# 4-DDR3_MEMORY.net
KiCad netlist of a schematic drawn in Altium Designer
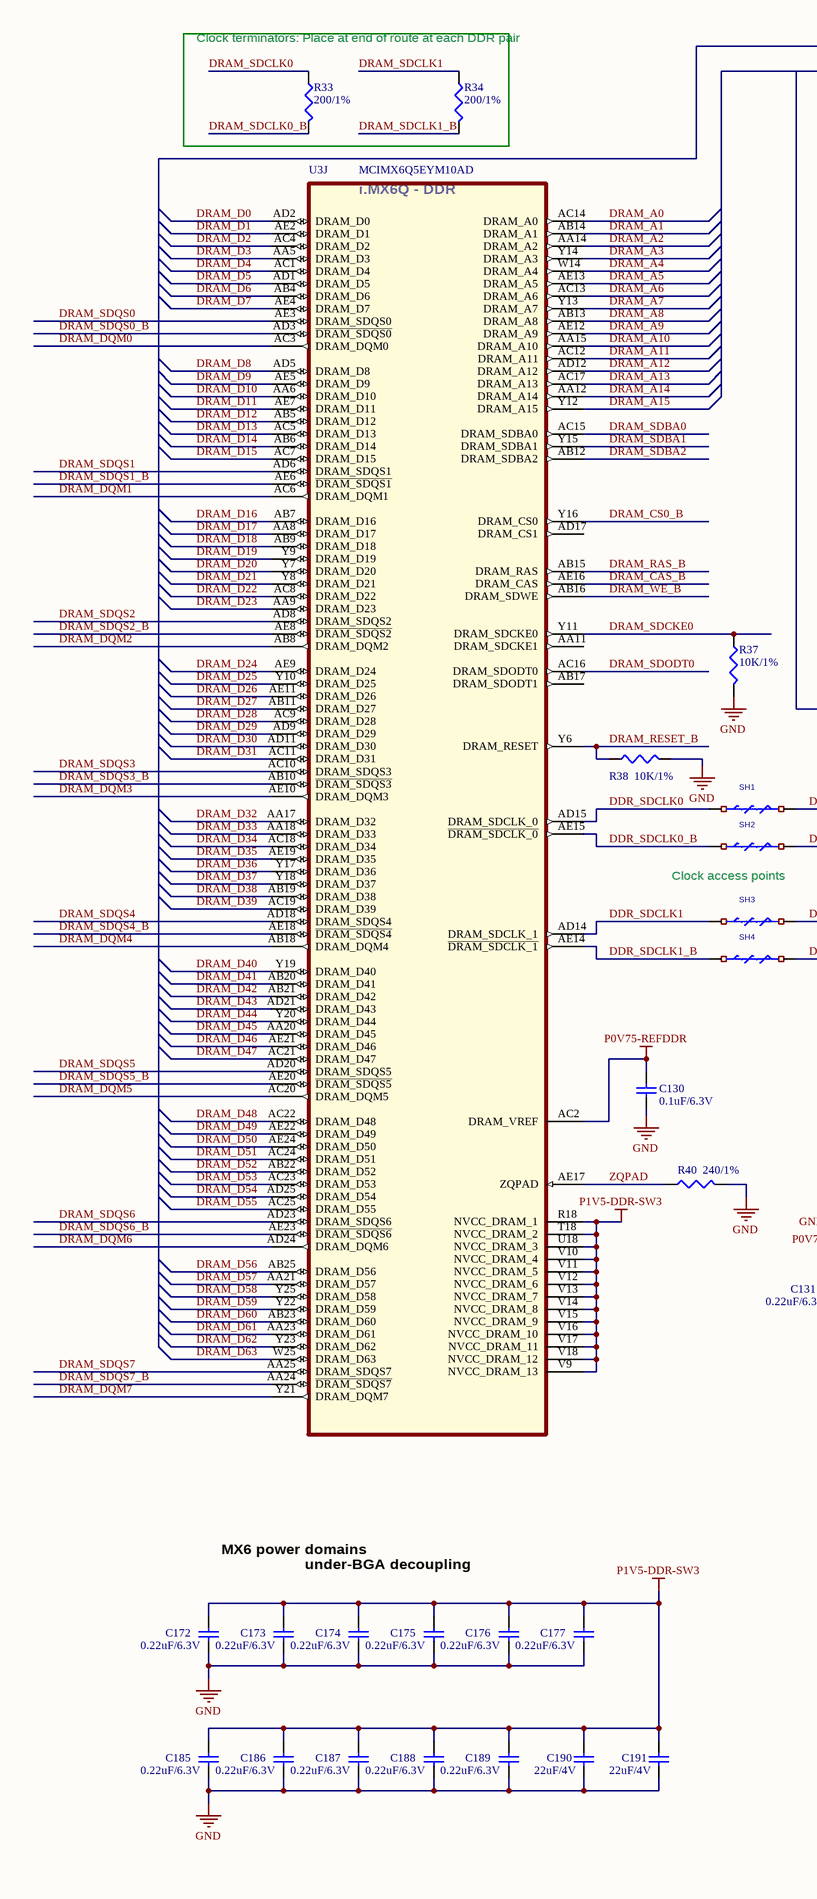
[diagram p0: 4-DDR3_MEMORY.SchDoc, left]
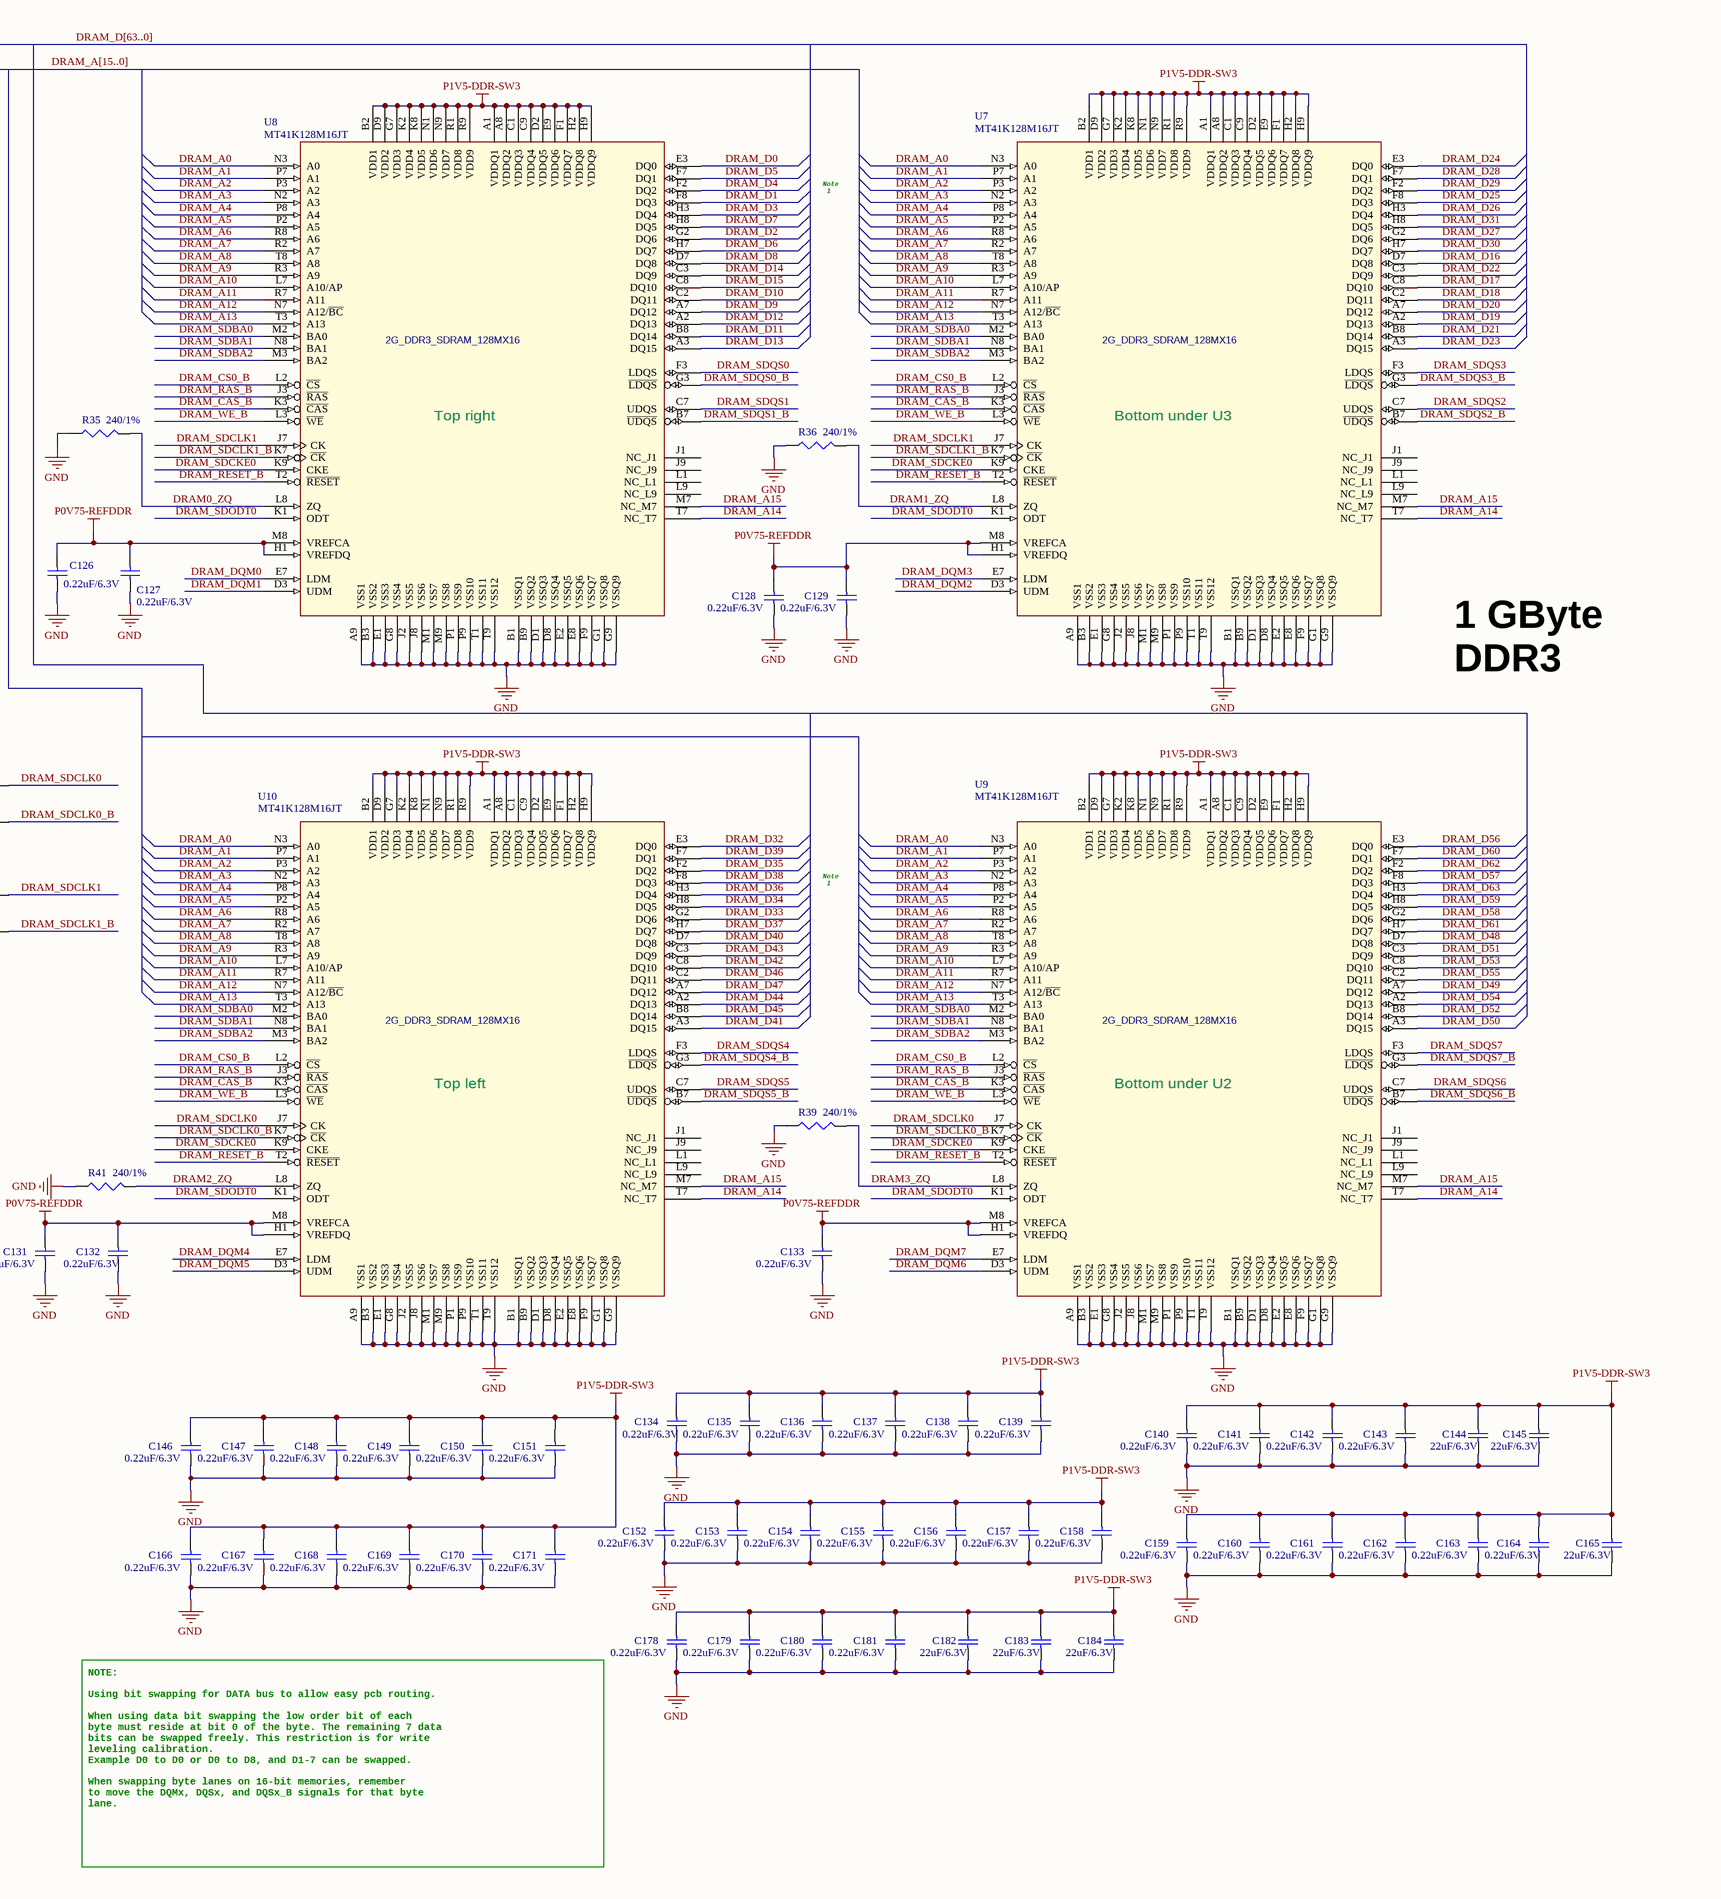
[diagram p1: 4-DDR3_MEMORY.SchDoc, right]

(export (version "E")
  (design (tool "Eeschema 10.0.6"))
  (components
    (comp (ref "C126")
      (value "0.22uF/6.3V")
      (footprint "0402_CC")
      (description "Capacitor")
      (fields (field (name "PUBLISHER") "Altium Limited"))
      (libsource (lib "Miscellaneous Devices") (part "Cap"))
    )
    (comp (ref "C127")
      (value "0.22uF/6.3V")
      (footprint "0402_CC")
      (description "Capacitor")
      (fields (field (name "PUBLISHER") "Altium Limited"))
      (libsource (lib "Miscellaneous Devices") (part "Cap"))
    )
    (comp (ref "C128")
      (value "0.22uF/6.3V")
      (footprint "0402_CC")
      (description "Capacitor")
      (fields (field (name "PUBLISHER") "Altium Limited"))
      (libsource (lib "Miscellaneous Devices") (part "Cap"))
    )
    (comp (ref "C129")
      (value "0.22uF/6.3V")
      (footprint "0402_CC")
      (description "Capacitor")
      (fields (field (name "PUBLISHER") "Altium Limited"))
      (libsource (lib "Miscellaneous Devices") (part "Cap"))
    )
    (comp (ref "C130")
      (value "0.1uF/6.3V")
      (footprint "0402_CC")
      (description "Capacitor")
      (fields (field (name "PUBLISHER") "Altium Limited"))
      (libsource (lib "Miscellaneous Devices") (part "Cap"))
    )
    (comp (ref "C131")
      (value "0.22uF/6.3V")
      (footprint "0402_CC")
      (description "Capacitor")
      (fields (field (name "PUBLISHER") "Altium Limited"))
      (libsource (lib "Miscellaneous Devices") (part "Cap"))
    )
    (comp (ref "C132")
      (value "0.22uF/6.3V")
      (footprint "0402_CC")
      (description "Capacitor")
      (fields (field (name "PUBLISHER") "Altium Limited"))
      (libsource (lib "Miscellaneous Devices") (part "Cap"))
    )
    (comp (ref "C133")
      (value "0.22uF/6.3V")
      (footprint "0402_CC")
      (description "Capacitor")
      (fields (field (name "PUBLISHER") "Altium Limited"))
      (libsource (lib "Miscellaneous Devices") (part "Cap"))
    )
    (comp (ref "C134")
      (value "0.22uF/6.3V")
      (footprint "0402_CC")
      (description "Capacitor")
      (fields (field (name "PUBLISHER") "Altium Limited"))
      (libsource (lib "Miscellaneous Devices") (part "Cap"))
    )
    (comp (ref "C135")
      (value "0.22uF/6.3V")
      (footprint "0402_CC")
      (description "Capacitor")
      (fields (field (name "PUBLISHER") "Altium Limited"))
      (libsource (lib "Miscellaneous Devices") (part "Cap"))
    )
    (comp (ref "C136")
      (value "0.22uF/6.3V")
      (footprint "0402_CC")
      (description "Capacitor")
      (fields (field (name "PUBLISHER") "Altium Limited"))
      (libsource (lib "Miscellaneous Devices") (part "Cap"))
    )
    (comp (ref "C137")
      (value "0.22uF/6.3V")
      (footprint "0402_CC")
      (description "Capacitor")
      (fields (field (name "PUBLISHER") "Altium Limited"))
      (libsource (lib "Miscellaneous Devices") (part "Cap"))
    )
    (comp (ref "C138")
      (value "0.22uF/6.3V")
      (footprint "0402_CC")
      (description "Capacitor")
      (fields (field (name "PUBLISHER") "Altium Limited"))
      (libsource (lib "Miscellaneous Devices") (part "Cap"))
    )
    (comp (ref "C139")
      (value "0.22uF/6.3V")
      (footprint "0402_CC")
      (description "Capacitor")
      (fields (field (name "PUBLISHER") "Altium Limited"))
      (libsource (lib "Miscellaneous Devices") (part "Cap"))
    )
    (comp (ref "C140")
      (value "0.22uF/6.3V")
      (footprint "0402_CC")
      (description "Capacitor")
      (fields (field (name "PUBLISHER") "Altium Limited"))
      (libsource (lib "Miscellaneous Devices") (part "Cap"))
    )
    (comp (ref "C141")
      (value "0.22uF/6.3V")
      (footprint "0402_CC")
      (description "Capacitor")
      (fields (field (name "PUBLISHER") "Altium Limited"))
      (libsource (lib "Miscellaneous Devices") (part "Cap"))
    )
    (comp (ref "C142")
      (value "0.22uF/6.3V")
      (footprint "0402_CC")
      (description "Capacitor")
      (fields (field (name "PUBLISHER") "Altium Limited"))
      (libsource (lib "Miscellaneous Devices") (part "Cap"))
    )
    (comp (ref "C143")
      (value "0.22uF/6.3V")
      (footprint "0402_CC")
      (description "Capacitor")
      (fields (field (name "PUBLISHER") "Altium Limited"))
      (libsource (lib "Miscellaneous Devices") (part "Cap"))
    )
    (comp (ref "C144")
      (value "22uF/6.3V")
      (footprint "0805_CC")
      (description "Capacitor")
      (fields (field (name "PUBLISHER") "Altium Limited"))
      (libsource (lib "Miscellaneous Devices") (part "Cap"))
    )
    (comp (ref "C145")
      (value "22uF/6.3V")
      (footprint "0805_CC")
      (description "Capacitor")
      (fields (field (name "PUBLISHER") "Altium Limited"))
      (libsource (lib "Miscellaneous Devices") (part "Cap"))
    )
    (comp (ref "C146")
      (value "0.22uF/6.3V")
      (footprint "0402_CC")
      (description "Capacitor")
      (fields (field (name "PUBLISHER") "Altium Limited"))
      (libsource (lib "Miscellaneous Devices") (part "Cap"))
    )
    (comp (ref "C147")
      (value "0.22uF/6.3V")
      (footprint "0402_CC")
      (description "Capacitor")
      (fields (field (name "PUBLISHER") "Altium Limited"))
      (libsource (lib "Miscellaneous Devices") (part "Cap"))
    )
    (comp (ref "C148")
      (value "0.22uF/6.3V")
      (footprint "0402_CC")
      (description "Capacitor")
      (fields (field (name "PUBLISHER") "Altium Limited"))
      (libsource (lib "Miscellaneous Devices") (part "Cap"))
    )
    (comp (ref "C149")
      (value "0.22uF/6.3V")
      (footprint "0402_CC")
      (description "Capacitor")
      (fields (field (name "PUBLISHER") "Altium Limited"))
      (libsource (lib "Miscellaneous Devices") (part "Cap"))
    )
    (comp (ref "C150")
      (value "0.22uF/6.3V")
      (footprint "0402_CC")
      (description "Capacitor")
      (fields (field (name "PUBLISHER") "Altium Limited"))
      (libsource (lib "Miscellaneous Devices") (part "Cap"))
    )
    (comp (ref "C151")
      (value "0.22uF/6.3V")
      (footprint "0402_CC")
      (description "Capacitor")
      (fields (field (name "PUBLISHER") "Altium Limited"))
      (libsource (lib "Miscellaneous Devices") (part "Cap"))
    )
    (comp (ref "C152")
      (value "0.22uF/6.3V")
      (footprint "0402_CC")
      (description "Capacitor")
      (fields (field (name "PUBLISHER") "Altium Limited"))
      (libsource (lib "Miscellaneous Devices") (part "Cap"))
    )
    (comp (ref "C153")
      (value "0.22uF/6.3V")
      (footprint "0402_CC")
      (description "Capacitor")
      (fields (field (name "PUBLISHER") "Altium Limited"))
      (libsource (lib "Miscellaneous Devices") (part "Cap"))
    )
    (comp (ref "C154")
      (value "0.22uF/6.3V")
      (footprint "0402_CC")
      (description "Capacitor")
      (fields (field (name "PUBLISHER") "Altium Limited"))
      (libsource (lib "Miscellaneous Devices") (part "Cap"))
    )
    (comp (ref "C155")
      (value "0.22uF/6.3V")
      (footprint "0402_CC")
      (description "Capacitor")
      (fields (field (name "PUBLISHER") "Altium Limited"))
      (libsource (lib "Miscellaneous Devices") (part "Cap"))
    )
    (comp (ref "C156")
      (value "0.22uF/6.3V")
      (footprint "0402_CC")
      (description "Capacitor")
      (fields (field (name "PUBLISHER") "Altium Limited"))
      (libsource (lib "Miscellaneous Devices") (part "Cap"))
    )
    (comp (ref "C157")
      (value "0.22uF/6.3V")
      (footprint "0402_CC")
      (description "Capacitor")
      (fields (field (name "PUBLISHER") "Altium Limited"))
      (libsource (lib "Miscellaneous Devices") (part "Cap"))
    )
    (comp (ref "C158")
      (value "0.22uF/6.3V")
      (footprint "0402_CC")
      (description "Capacitor")
      (fields (field (name "PUBLISHER") "Altium Limited"))
      (libsource (lib "Miscellaneous Devices") (part "Cap"))
    )
    (comp (ref "C159")
      (value "0.22uF/6.3V")
      (footprint "0402_CC")
      (description "Capacitor")
      (fields (field (name "PUBLISHER") "Altium Limited"))
      (libsource (lib "Miscellaneous Devices") (part "Cap"))
    )
    (comp (ref "C160")
      (value "0.22uF/6.3V")
      (footprint "0402_CC")
      (description "Capacitor")
      (fields (field (name "PUBLISHER") "Altium Limited"))
      (libsource (lib "Miscellaneous Devices") (part "Cap"))
    )
    (comp (ref "C161")
      (value "0.22uF/6.3V")
      (footprint "0402_CC")
      (description "Capacitor")
      (fields (field (name "PUBLISHER") "Altium Limited"))
      (libsource (lib "Miscellaneous Devices") (part "Cap"))
    )
    (comp (ref "C162")
      (value "0.22uF/6.3V")
      (footprint "0402_CC")
      (description "Capacitor")
      (fields (field (name "PUBLISHER") "Altium Limited"))
      (libsource (lib "Miscellaneous Devices") (part "Cap"))
    )
    (comp (ref "C163")
      (value "0.22uF/6.3V")
      (footprint "0402_CC")
      (description "Capacitor")
      (fields (field (name "PUBLISHER") "Altium Limited"))
      (libsource (lib "Miscellaneous Devices") (part "Cap"))
    )
    (comp (ref "C164")
      (value "0.22uF/6.3V")
      (footprint "0402_CC")
      (description "Capacitor")
      (fields (field (name "PUBLISHER") "Altium Limited"))
      (libsource (lib "Miscellaneous Devices") (part "Cap"))
    )
    (comp (ref "C165")
      (value "22uF/6.3V")
      (footprint "0805_CC")
      (description "Capacitor")
      (fields (field (name "PUBLISHER") "Altium Limited"))
      (libsource (lib "Miscellaneous Devices") (part "Cap"))
    )
    (comp (ref "C166")
      (value "0.22uF/6.3V")
      (footprint "0402_CC")
      (description "Capacitor")
      (fields (field (name "PUBLISHER") "Altium Limited"))
      (libsource (lib "Miscellaneous Devices") (part "Cap"))
    )
    (comp (ref "C167")
      (value "0.22uF/6.3V")
      (footprint "0402_CC")
      (description "Capacitor")
      (fields (field (name "PUBLISHER") "Altium Limited"))
      (libsource (lib "Miscellaneous Devices") (part "Cap"))
    )
    (comp (ref "C168")
      (value "0.22uF/6.3V")
      (footprint "0402_CC")
      (description "Capacitor")
      (fields (field (name "PUBLISHER") "Altium Limited"))
      (libsource (lib "Miscellaneous Devices") (part "Cap"))
    )
    (comp (ref "C169")
      (value "0.22uF/6.3V")
      (footprint "0402_CC")
      (description "Capacitor")
      (fields (field (name "PUBLISHER") "Altium Limited"))
      (libsource (lib "Miscellaneous Devices") (part "Cap"))
    )
    (comp (ref "C170")
      (value "0.22uF/6.3V")
      (footprint "0402_CC")
      (description "Capacitor")
      (fields (field (name "PUBLISHER") "Altium Limited"))
      (libsource (lib "Miscellaneous Devices") (part "Cap"))
    )
    (comp (ref "C171")
      (value "0.22uF/6.3V")
      (footprint "0402_CC")
      (description "Capacitor")
      (fields (field (name "PUBLISHER") "Altium Limited"))
      (libsource (lib "Miscellaneous Devices") (part "Cap"))
    )
    (comp (ref "C172")
      (value "0.22uF/6.3V")
      (footprint "0201_CC")
      (description "Capacitor")
      (fields (field (name "PUBLISHER") "Altium Limited"))
      (libsource (lib "Miscellaneous Devices") (part "Cap"))
    )
    (comp (ref "C173")
      (value "0.22uF/6.3V")
      (footprint "0201_CC")
      (description "Capacitor")
      (fields (field (name "PUBLISHER") "Altium Limited"))
      (libsource (lib "Miscellaneous Devices") (part "Cap"))
    )
    (comp (ref "C174")
      (value "0.22uF/6.3V")
      (footprint "0201_CC")
      (description "Capacitor")
      (fields (field (name "PUBLISHER") "Altium Limited"))
      (libsource (lib "Miscellaneous Devices") (part "Cap"))
    )
    (comp (ref "C175")
      (value "0.22uF/6.3V")
      (footprint "0201_CC")
      (description "Capacitor")
      (fields (field (name "PUBLISHER") "Altium Limited"))
      (libsource (lib "Miscellaneous Devices") (part "Cap"))
    )
    (comp (ref "C176")
      (value "0.22uF/6.3V")
      (footprint "0201_CC")
      (description "Capacitor")
      (fields (field (name "PUBLISHER") "Altium Limited"))
      (libsource (lib "Miscellaneous Devices") (part "Cap"))
    )
    (comp (ref "C177")
      (value "0.22uF/6.3V")
      (footprint "0201_CC")
      (description "Capacitor")
      (fields (field (name "PUBLISHER") "Altium Limited"))
      (libsource (lib "Miscellaneous Devices") (part "Cap"))
    )
    (comp (ref "C178")
      (value "0.22uF/6.3V")
      (footprint "0402_CC")
      (description "Capacitor")
      (fields (field (name "PUBLISHER") "Altium Limited"))
      (libsource (lib "Miscellaneous Devices") (part "Cap"))
    )
    (comp (ref "C179")
      (value "0.22uF/6.3V")
      (footprint "0402_CC")
      (description "Capacitor")
      (fields (field (name "PUBLISHER") "Altium Limited"))
      (libsource (lib "Miscellaneous Devices") (part "Cap"))
    )
    (comp (ref "C180")
      (value "0.22uF/6.3V")
      (footprint "0402_CC")
      (description "Capacitor")
      (fields (field (name "PUBLISHER") "Altium Limited"))
      (libsource (lib "Miscellaneous Devices") (part "Cap"))
    )
    (comp (ref "C181")
      (value "0.22uF/6.3V")
      (footprint "0402_CC")
      (description "Capacitor")
      (fields (field (name "PUBLISHER") "Altium Limited"))
      (libsource (lib "Miscellaneous Devices") (part "Cap"))
    )
    (comp (ref "C182")
      (value "22uF/6.3V")
      (footprint "0805_CC")
      (description "Capacitor")
      (fields (field (name "PUBLISHER") "Altium Limited"))
      (libsource (lib "Miscellaneous Devices") (part "Cap"))
    )
    (comp (ref "C183")
      (value "22uF/6.3V")
      (footprint "0805_CC")
      (description "Capacitor")
      (fields (field (name "PUBLISHER") "Altium Limited"))
      (libsource (lib "Miscellaneous Devices") (part "Cap"))
    )
    (comp (ref "C184")
      (value "22uF/6.3V")
      (footprint "0805_CC")
      (description "Capacitor")
      (fields (field (name "PUBLISHER") "Altium Limited"))
      (libsource (lib "Miscellaneous Devices") (part "Cap"))
    )
    (comp (ref "C185")
      (value "0.22uF/6.3V")
      (footprint "0201_CC")
      (description "Capacitor")
      (fields (field (name "PUBLISHER") "Altium Limited"))
      (libsource (lib "Miscellaneous Devices") (part "Cap"))
    )
    (comp (ref "C186")
      (value "0.22uF/6.3V")
      (footprint "0201_CC")
      (description "Capacitor")
      (fields (field (name "PUBLISHER") "Altium Limited"))
      (libsource (lib "Miscellaneous Devices") (part "Cap"))
    )
    (comp (ref "C187")
      (value "0.22uF/6.3V")
      (footprint "0201_CC")
      (description "Capacitor")
      (fields (field (name "PUBLISHER") "Altium Limited"))
      (libsource (lib "Miscellaneous Devices") (part "Cap"))
    )
    (comp (ref "C188")
      (value "0.22uF/6.3V")
      (footprint "0201_CC")
      (description "Capacitor")
      (fields (field (name "PUBLISHER") "Altium Limited"))
      (libsource (lib "Miscellaneous Devices") (part "Cap"))
    )
    (comp (ref "C189")
      (value "0.22uF/6.3V")
      (footprint "0201_CC")
      (description "Capacitor")
      (fields (field (name "PUBLISHER") "Altium Limited"))
      (libsource (lib "Miscellaneous Devices") (part "Cap"))
    )
    (comp (ref "C190")
      (value "22uF/4V")
      (footprint "0603_CC")
      (description "Capacitor")
      (fields (field (name "PUBLISHER") "Altium Limited"))
      (libsource (lib "Miscellaneous Devices") (part "Cap"))
    )
    (comp (ref "C191")
      (value "22uF/4V")
      (footprint "0603_CC")
      (description "Capacitor")
      (fields (field (name "PUBLISHER") "Altium Limited"))
      (libsource (lib "Miscellaneous Devices") (part "Cap"))
    )
    (comp (ref "R33")
      (value "200/1%")
      (footprint "0402_CC")
      (description "Resistor")
      (fields (field (name "PUBLISHER") "Altium Limited"))
      (libsource (lib "Miscellaneous Devices") (part "Res3"))
    )
    (comp (ref "R34")
      (value "200/1%")
      (footprint "0402_CC")
      (description "Resistor")
      (fields (field (name "PUBLISHER") "Altium Limited"))
      (libsource (lib "Miscellaneous Devices") (part "Res3"))
    )
    (comp (ref "R35")
      (value "240/1%")
      (footprint "0402_CC")
      (description "Resistor")
      (fields (field (name "PUBLISHER") "Altium Limited"))
      (libsource (lib "Miscellaneous Devices") (part "Res3"))
    )
    (comp (ref "R36")
      (value "240/1%")
      (footprint "0402_CC")
      (description "Resistor")
      (fields (field (name "PUBLISHER") "Altium Limited"))
      (libsource (lib "Miscellaneous Devices") (part "Res3"))
    )
    (comp (ref "R37")
      (value "10K/1%")
      (footprint "0402_CC")
      (description "Resistor")
      (fields (field (name "PUBLISHER") "Altium Limited"))
      (libsource (lib "Miscellaneous Devices") (part "Res3"))
    )
    (comp (ref "R38")
      (value "10K/1%")
      (footprint "0402_CC")
      (description "Resistor")
      (fields (field (name "PUBLISHER") "Altium Limited"))
      (libsource (lib "Miscellaneous Devices") (part "Res3"))
    )
    (comp (ref "R39")
      (value "240/1%")
      (footprint "0402_CC")
      (description "Resistor")
      (fields (field (name "PUBLISHER") "Altium Limited"))
      (libsource (lib "Miscellaneous Devices") (part "Res3"))
    )
    (comp (ref "R40")
      (value "240/1%")
      (footprint "0402_CC")
      (description "Resistor")
      (fields (field (name "PUBLISHER") "Altium Limited"))
      (libsource (lib "Miscellaneous Devices") (part "Res3"))
    )
    (comp (ref "R41")
      (value "240/1%")
      (footprint "0402_CC")
      (description "Resistor")
      (fields (field (name "PUBLISHER") "Altium Limited"))
      (libsource (lib "Miscellaneous Devices") (part "Res3"))
    )
    (comp (ref "SH1")
      (value "0")
      (footprint "0201_CC")
      (description "ZERO OHM CUT TRACE 0201 PADS; NO PART TO ORDER")
      (libsource (lib "*") (part "RES_SHORT-2"))
    )
    (comp (ref "SH2")
      (value "0")
      (footprint "0201_CC")
      (description "ZERO OHM CUT TRACE 0201 PADS; NO PART TO ORDER")
      (libsource (lib "*") (part "RES_SHORT-2"))
    )
    (comp (ref "SH3")
      (value "0")
      (footprint "0201_CC")
      (description "ZERO OHM CUT TRACE 0201 PADS; NO PART TO ORDER")
      (libsource (lib "*") (part "RES_SHORT-2"))
    )
    (comp (ref "SH4")
      (value "0")
      (footprint "0201_CC")
      (description "ZERO OHM CUT TRACE 0201 PADS; NO PART TO ORDER")
      (libsource (lib "*") (part "RES_SHORT-2"))
    )
    (comp (ref "U3")
      (value "MCIMX6Q5EYM10AD")
      (footprint "FCPBGA")
      (description "IC MCU MX6QUAD ARM CORTEX-A9 FCPBGA624")
      (libsource (lib "*") (part "PCIMX6Q6VV1A"))
    )
    (comp (ref "U7")
      (value "MT41K128M16JT")
      (footprint "BGA96")
      (description "IC MEM DDR3 SDRAM 2Gb 128MX16 1.35V FBGA96")
      (libsource (lib "*") (part "2G_DDR3_SDRAM_128MX16_96P"))
    )
    (comp (ref "U8")
      (value "MT41K128M16JT")
      (footprint "BGA96")
      (description "IC MEM DDR3 SDRAM 2Gb 128MX16 1.35V FBGA96")
      (libsource (lib "*") (part "2G_DDR3_SDRAM_128MX16_96P"))
    )
    (comp (ref "U9")
      (value "MT41K128M16JT")
      (footprint "BGA96")
      (description "IC MEM DDR3 SDRAM 2Gb 128MX16 1.35V FBGA96")
      (libsource (lib "*") (part "2G_DDR3_SDRAM_128MX16_96P"))
    )
    (comp (ref "U10")
      (value "MT41K128M16JT")
      (footprint "BGA96")
      (description "IC MEM DDR3 SDRAM 2Gb 128MX16 1.35V FBGA96")
      (libsource (lib "*") (part "2G_DDR3_SDRAM_128MX16_96P"))
    )
  )
  (nets
    (net (code "1") (name "/DDR_SDCLK0") (class "Default")
      (node (ref "SH1") (pin "1") (pinfunction "1_1") (pintype "passive"))
      (node (ref "U3") (pin "AD15") (pinfunction "DRAM_SDCLK_0_AD15") (pintype "output"))
    )
    (net (code "2") (name "/DDR_SDCLK0_B") (class "Default")
      (node (ref "SH2") (pin "1") (pinfunction "1_1") (pintype "passive"))
      (node (ref "U3") (pin "AE15") (pinfunction "~{DRAM_SDCLK_0}_AE15") (pintype "output"))
    )
    (net (code "3") (name "/DDR_SDCLK1") (class "Default")
      (node (ref "SH3") (pin "1") (pinfunction "1_1") (pintype "passive"))
      (node (ref "U3") (pin "AD14") (pinfunction "DRAM_SDCLK_1_AD14") (pintype "output"))
    )
    (net (code "4") (name "/DDR_SDCLK1_B") (class "Default")
      (node (ref "SH4") (pin "1") (pinfunction "1_1") (pintype "passive"))
      (node (ref "U3") (pin "AE14") (pinfunction "~{DRAM_SDCLK_1}_AE14") (pintype "output"))
    )
    (net (code "5") (name "/DRAM0_ZQ") (class "Default")
      (node (ref "R35") (pin "2") (pinfunction "2_2") (pintype "passive"))
      (node (ref "U8") (pin "L8") (pinfunction "ZQ_L8") (pintype "input"))
    )
    (net (code "6") (name "/DRAM1_ZQ") (class "Default")
      (node (ref "R36") (pin "2") (pinfunction "2_2") (pintype "passive"))
      (node (ref "U7") (pin "L8") (pinfunction "ZQ_L8") (pintype "input"))
    )
    (net (code "7") (name "/DRAM2_ZQ") (class "Default")
      (node (ref "R41") (pin "2") (pinfunction "2_2") (pintype "passive"))
      (node (ref "U10") (pin "L8") (pinfunction "ZQ_L8") (pintype "input"))
    )
    (net (code "8") (name "/DRAM3_ZQ") (class "Default")
      (node (ref "R39") (pin "2") (pinfunction "2_2") (pintype "passive"))
      (node (ref "U9") (pin "L8") (pinfunction "ZQ_L8") (pintype "input"))
    )
    (net (code "9") (name "/DRAM_A0") (class "Default")
      (node (ref "U10") (pin "N3") (pinfunction "A0_N3") (pintype "input"))
      (node (ref "U3") (pin "AC14") (pinfunction "DRAM_A0_AC14") (pintype "output"))
      (node (ref "U7") (pin "N3") (pinfunction "A0_N3") (pintype "input"))
      (node (ref "U8") (pin "N3") (pinfunction "A0_N3") (pintype "input"))
      (node (ref "U9") (pin "N3") (pinfunction "A0_N3") (pintype "input"))
    )
    (net (code "10") (name "/DRAM_A1") (class "Default")
      (node (ref "U10") (pin "P7") (pinfunction "A1_P7") (pintype "input"))
      (node (ref "U3") (pin "AB14") (pinfunction "DRAM_A1_AB14") (pintype "output"))
      (node (ref "U7") (pin "P7") (pinfunction "A1_P7") (pintype "input"))
      (node (ref "U8") (pin "P7") (pinfunction "A1_P7") (pintype "input"))
      (node (ref "U9") (pin "P7") (pinfunction "A1_P7") (pintype "input"))
    )
    (net (code "11") (name "/DRAM_A2") (class "Default")
      (node (ref "U10") (pin "P3") (pinfunction "A2_P3") (pintype "input"))
      (node (ref "U3") (pin "AA14") (pinfunction "DRAM_A2_AA14") (pintype "output"))
      (node (ref "U7") (pin "P3") (pinfunction "A2_P3") (pintype "input"))
      (node (ref "U8") (pin "P3") (pinfunction "A2_P3") (pintype "input"))
      (node (ref "U9") (pin "P3") (pinfunction "A2_P3") (pintype "input"))
    )
    (net (code "12") (name "/DRAM_A3") (class "Default")
      (node (ref "U10") (pin "N2") (pinfunction "A3_N2") (pintype "input"))
      (node (ref "U3") (pin "Y14") (pinfunction "DRAM_A3_Y14") (pintype "output"))
      (node (ref "U7") (pin "N2") (pinfunction "A3_N2") (pintype "input"))
      (node (ref "U8") (pin "N2") (pinfunction "A3_N2") (pintype "input"))
      (node (ref "U9") (pin "N2") (pinfunction "A3_N2") (pintype "input"))
    )
    (net (code "13") (name "/DRAM_A4") (class "Default")
      (node (ref "U10") (pin "P8") (pinfunction "A4_P8") (pintype "input"))
      (node (ref "U3") (pin "W14") (pinfunction "DRAM_A4_W14") (pintype "output"))
      (node (ref "U7") (pin "P8") (pinfunction "A4_P8") (pintype "input"))
      (node (ref "U8") (pin "P8") (pinfunction "A4_P8") (pintype "input"))
      (node (ref "U9") (pin "P8") (pinfunction "A4_P8") (pintype "input"))
    )
    (net (code "14") (name "/DRAM_A5") (class "Default")
      (node (ref "U10") (pin "P2") (pinfunction "A5_P2") (pintype "input"))
      (node (ref "U3") (pin "AE13") (pinfunction "DRAM_A5_AE13") (pintype "output"))
      (node (ref "U7") (pin "P2") (pinfunction "A5_P2") (pintype "input"))
      (node (ref "U8") (pin "P2") (pinfunction "A5_P2") (pintype "input"))
      (node (ref "U9") (pin "P2") (pinfunction "A5_P2") (pintype "input"))
    )
    (net (code "15") (name "/DRAM_A6") (class "Default")
      (node (ref "U10") (pin "R8") (pinfunction "A6_R8") (pintype "input"))
      (node (ref "U3") (pin "AC13") (pinfunction "DRAM_A6_AC13") (pintype "output"))
      (node (ref "U7") (pin "R8") (pinfunction "A6_R8") (pintype "input"))
      (node (ref "U8") (pin "R8") (pinfunction "A6_R8") (pintype "input"))
      (node (ref "U9") (pin "R8") (pinfunction "A6_R8") (pintype "input"))
    )
    (net (code "16") (name "/DRAM_A7") (class "Default")
      (node (ref "U10") (pin "R2") (pinfunction "A7_R2") (pintype "input"))
      (node (ref "U3") (pin "Y13") (pinfunction "DRAM_A7_Y13") (pintype "output"))
      (node (ref "U7") (pin "R2") (pinfunction "A7_R2") (pintype "input"))
      (node (ref "U8") (pin "R2") (pinfunction "A7_R2") (pintype "input"))
      (node (ref "U9") (pin "R2") (pinfunction "A7_R2") (pintype "input"))
    )
    (net (code "17") (name "/DRAM_A8") (class "Default")
      (node (ref "U10") (pin "T8") (pinfunction "A8_T8") (pintype "input"))
      (node (ref "U3") (pin "AB13") (pinfunction "DRAM_A8_AB13") (pintype "output"))
      (node (ref "U7") (pin "T8") (pinfunction "A8_T8") (pintype "input"))
      (node (ref "U8") (pin "T8") (pinfunction "A8_T8") (pintype "input"))
      (node (ref "U9") (pin "T8") (pinfunction "A8_T8") (pintype "input"))
    )
    (net (code "18") (name "/DRAM_A9") (class "Default")
      (node (ref "U10") (pin "R3") (pinfunction "A9_R3") (pintype "input"))
      (node (ref "U3") (pin "AE12") (pinfunction "DRAM_A9_AE12") (pintype "output"))
      (node (ref "U7") (pin "R3") (pinfunction "A9_R3") (pintype "input"))
      (node (ref "U8") (pin "R3") (pinfunction "A9_R3") (pintype "input"))
      (node (ref "U9") (pin "R3") (pinfunction "A9_R3") (pintype "input"))
    )
    (net (code "19") (name "/DRAM_A10") (class "Default")
      (node (ref "U10") (pin "L7") (pinfunction "A10/AP_L7") (pintype "input"))
      (node (ref "U3") (pin "AA15") (pinfunction "DRAM_A10_AA15") (pintype "output"))
      (node (ref "U7") (pin "L7") (pinfunction "A10/AP_L7") (pintype "input"))
      (node (ref "U8") (pin "L7") (pinfunction "A10/AP_L7") (pintype "input"))
      (node (ref "U9") (pin "L7") (pinfunction "A10/AP_L7") (pintype "input"))
    )
    (net (code "20") (name "/DRAM_A11") (class "Default")
      (node (ref "U10") (pin "R7") (pinfunction "A11_R7") (pintype "input"))
      (node (ref "U3") (pin "AC12") (pinfunction "DRAM_A11_AC12") (pintype "output"))
      (node (ref "U7") (pin "R7") (pinfunction "A11_R7") (pintype "input"))
      (node (ref "U8") (pin "R7") (pinfunction "A11_R7") (pintype "input"))
      (node (ref "U9") (pin "R7") (pinfunction "A11_R7") (pintype "input"))
    )
    (net (code "21") (name "/DRAM_A12") (class "Default")
      (node (ref "U10") (pin "N7") (pinfunction "A12/~{BC}_N7") (pintype "input"))
      (node (ref "U3") (pin "AD12") (pinfunction "DRAM_A12_AD12") (pintype "output"))
      (node (ref "U7") (pin "N7") (pinfunction "A12/~{BC}_N7") (pintype "input"))
      (node (ref "U8") (pin "N7") (pinfunction "A12/~{BC}_N7") (pintype "input"))
      (node (ref "U9") (pin "N7") (pinfunction "A12/~{BC}_N7") (pintype "input"))
    )
    (net (code "22") (name "/DRAM_A13") (class "Default")
      (node (ref "U10") (pin "T3") (pinfunction "A13_T3") (pintype "input"))
      (node (ref "U3") (pin "AC17") (pinfunction "DRAM_A13_AC17") (pintype "output"))
      (node (ref "U7") (pin "T3") (pinfunction "A13_T3") (pintype "input"))
      (node (ref "U8") (pin "T3") (pinfunction "A13_T3") (pintype "input"))
      (node (ref "U9") (pin "T3") (pinfunction "A13_T3") (pintype "input"))
    )
    (net (code "23") (name "/DRAM_A14") (class "Default")
      (node (ref "U10") (pin "T7") (pinfunction "NC_T7_T7") (pintype "passive"))
      (node (ref "U3") (pin "AA12") (pinfunction "DRAM_A14_AA12") (pintype "output"))
      (node (ref "U7") (pin "T7") (pinfunction "NC_T7_T7") (pintype "passive"))
      (node (ref "U8") (pin "T7") (pinfunction "NC_T7_T7") (pintype "passive"))
      (node (ref "U9") (pin "T7") (pinfunction "NC_T7_T7") (pintype "passive"))
    )
    (net (code "24") (name "/DRAM_A15") (class "Default")
      (node (ref "U10") (pin "M7") (pinfunction "NC_M7_M7") (pintype "passive"))
      (node (ref "U3") (pin "Y12") (pinfunction "DRAM_A15_Y12") (pintype "output"))
      (node (ref "U7") (pin "M7") (pinfunction "NC_M7_M7") (pintype "passive"))
      (node (ref "U8") (pin "M7") (pinfunction "NC_M7_M7") (pintype "passive"))
      (node (ref "U9") (pin "M7") (pinfunction "NC_M7_M7") (pintype "passive"))
    )
    (net (code "26") (name "/DRAM_CAS_B") (class "Default")
      (node (ref "U10") (pin "K3") (pinfunction "~{CAS}_K3") (pintype "input"))
      (node (ref "U3") (pin "AE16") (pinfunction "DRAM_CAS_AE16") (pintype "output"))
      (node (ref "U7") (pin "K3") (pinfunction "~{CAS}_K3") (pintype "input"))
      (node (ref "U8") (pin "K3") (pinfunction "~{CAS}_K3") (pintype "input"))
      (node (ref "U9") (pin "K3") (pinfunction "~{CAS}_K3") (pintype "input"))
    )
    (net (code "27") (name "/DRAM_CS0_B") (class "Default")
      (node (ref "U10") (pin "L2") (pinfunction "~{CS}_L2") (pintype "input"))
      (node (ref "U3") (pin "Y16") (pinfunction "DRAM_CS0_Y16") (pintype "output"))
      (node (ref "U7") (pin "L2") (pinfunction "~{CS}_L2") (pintype "input"))
      (node (ref "U8") (pin "L2") (pinfunction "~{CS}_L2") (pintype "input"))
      (node (ref "U9") (pin "L2") (pinfunction "~{CS}_L2") (pintype "input"))
    )
    (net (code "28") (name "/DRAM_D0") (class "Default")
      (node (ref "U3") (pin "AD2") (pinfunction "DRAM_D0_AD2") (pintype "bidirectional"))
      (node (ref "U8") (pin "E3") (pinfunction "DQ0_E3") (pintype "bidirectional"))
    )
    (net (code "29") (name "/DRAM_D1") (class "Default")
      (node (ref "U3") (pin "AE2") (pinfunction "DRAM_D1_AE2") (pintype "bidirectional"))
      (node (ref "U8") (pin "F8") (pinfunction "DQ3_F8") (pintype "bidirectional"))
    )
    (net (code "30") (name "/DRAM_D2") (class "Default")
      (node (ref "U3") (pin "AC4") (pinfunction "DRAM_D2_AC4") (pintype "bidirectional"))
      (node (ref "U8") (pin "G2") (pinfunction "DQ6_G2") (pintype "bidirectional"))
    )
    (net (code "31") (name "/DRAM_D3") (class "Default")
      (node (ref "U3") (pin "AA5") (pinfunction "DRAM_D3_AA5") (pintype "bidirectional"))
      (node (ref "U8") (pin "H3") (pinfunction "DQ4_H3") (pintype "bidirectional"))
    )
    (net (code "32") (name "/DRAM_D4") (class "Default")
      (node (ref "U3") (pin "AC1") (pinfunction "DRAM_D4_AC1") (pintype "bidirectional"))
      (node (ref "U8") (pin "F2") (pinfunction "DQ2_F2") (pintype "bidirectional"))
    )
    (net (code "33") (name "/DRAM_D5") (class "Default")
      (node (ref "U3") (pin "AD1") (pinfunction "DRAM_D5_AD1") (pintype "bidirectional"))
      (node (ref "U8") (pin "F7") (pinfunction "DQ1_F7") (pintype "bidirectional"))
    )
    (net (code "34") (name "/DRAM_D6") (class "Default")
      (node (ref "U3") (pin "AB4") (pinfunction "DRAM_D6_AB4") (pintype "bidirectional"))
      (node (ref "U8") (pin "H7") (pinfunction "DQ7_H7") (pintype "bidirectional"))
    )
    (net (code "35") (name "/DRAM_D7") (class "Default")
      (node (ref "U3") (pin "AE4") (pinfunction "DRAM_D7_AE4") (pintype "bidirectional"))
      (node (ref "U8") (pin "H8") (pinfunction "DQ5_H8") (pintype "bidirectional"))
    )
    (net (code "36") (name "/DRAM_D8") (class "Default")
      (node (ref "U3") (pin "AD5") (pinfunction "DRAM_D8_AD5") (pintype "bidirectional"))
      (node (ref "U8") (pin "D7") (pinfunction "DQ8_D7") (pintype "bidirectional"))
    )
    (net (code "37") (name "/DRAM_D9") (class "Default")
      (node (ref "U3") (pin "AE5") (pinfunction "DRAM_D9_AE5") (pintype "bidirectional"))
      (node (ref "U8") (pin "A7") (pinfunction "DQ12_A7") (pintype "bidirectional"))
    )
    (net (code "38") (name "/DRAM_D10") (class "Default")
      (node (ref "U3") (pin "AA6") (pinfunction "DRAM_D10_AA6") (pintype "bidirectional"))
      (node (ref "U8") (pin "C2") (pinfunction "DQ11_C2") (pintype "bidirectional"))
    )
    (net (code "39") (name "/DRAM_D11") (class "Default")
      (node (ref "U3") (pin "AE7") (pinfunction "DRAM_D11_AE7") (pintype "bidirectional"))
      (node (ref "U8") (pin "B8") (pinfunction "DQ14_B8") (pintype "bidirectional"))
    )
    (net (code "40") (name "/DRAM_D12") (class "Default")
      (node (ref "U3") (pin "AB5") (pinfunction "DRAM_D12_AB5") (pintype "bidirectional"))
      (node (ref "U8") (pin "A2") (pinfunction "DQ13_A2") (pintype "bidirectional"))
    )
    (net (code "41") (name "/DRAM_D13") (class "Default")
      (node (ref "U3") (pin "AC5") (pinfunction "DRAM_D13_AC5") (pintype "bidirectional"))
      (node (ref "U8") (pin "A3") (pinfunction "DQ15_A3") (pintype "bidirectional"))
    )
    (net (code "42") (name "/DRAM_D14") (class "Default")
      (node (ref "U3") (pin "AB6") (pinfunction "DRAM_D14_AB6") (pintype "bidirectional"))
      (node (ref "U8") (pin "C3") (pinfunction "DQ9_C3") (pintype "bidirectional"))
    )
    (net (code "43") (name "/DRAM_D15") (class "Default")
      (node (ref "U3") (pin "AC7") (pinfunction "DRAM_D15_AC7") (pintype "bidirectional"))
      (node (ref "U8") (pin "C8") (pinfunction "DQ10_C8") (pintype "bidirectional"))
    )
    (net (code "44") (name "/DRAM_D16") (class "Default")
      (node (ref "U3") (pin "AB7") (pinfunction "DRAM_D16_AB7") (pintype "bidirectional"))
      (node (ref "U7") (pin "D7") (pinfunction "DQ8_D7") (pintype "bidirectional"))
    )
    (net (code "45") (name "/DRAM_D17") (class "Default")
      (node (ref "U3") (pin "AA8") (pinfunction "DRAM_D17_AA8") (pintype "bidirectional"))
      (node (ref "U7") (pin "C8") (pinfunction "DQ10_C8") (pintype "bidirectional"))
    )
    (net (code "46") (name "/DRAM_D18") (class "Default")
      (node (ref "U3") (pin "AB9") (pinfunction "DRAM_D18_AB9") (pintype "bidirectional"))
      (node (ref "U7") (pin "C2") (pinfunction "DQ11_C2") (pintype "bidirectional"))
    )
    (net (code "47") (name "/DRAM_D19") (class "Default")
      (node (ref "U3") (pin "Y9") (pinfunction "DRAM_D19_Y9") (pintype "bidirectional"))
      (node (ref "U7") (pin "A2") (pinfunction "DQ13_A2") (pintype "bidirectional"))
    )
    (net (code "48") (name "/DRAM_D20") (class "Default")
      (node (ref "U3") (pin "Y7") (pinfunction "DRAM_D20_Y7") (pintype "bidirectional"))
      (node (ref "U7") (pin "A7") (pinfunction "DQ12_A7") (pintype "bidirectional"))
    )
    (net (code "49") (name "/DRAM_D21") (class "Default")
      (node (ref "U3") (pin "Y8") (pinfunction "DRAM_D21_Y8") (pintype "bidirectional"))
      (node (ref "U7") (pin "B8") (pinfunction "DQ14_B8") (pintype "bidirectional"))
    )
    (net (code "50") (name "/DRAM_D22") (class "Default")
      (node (ref "U3") (pin "AC8") (pinfunction "DRAM_D22_AC8") (pintype "bidirectional"))
      (node (ref "U7") (pin "C3") (pinfunction "DQ9_C3") (pintype "bidirectional"))
    )
    (net (code "51") (name "/DRAM_D23") (class "Default")
      (node (ref "U3") (pin "AA9") (pinfunction "DRAM_D23_AA9") (pintype "bidirectional"))
      (node (ref "U7") (pin "A3") (pinfunction "DQ15_A3") (pintype "bidirectional"))
    )
    (net (code "52") (name "/DRAM_D24") (class "Default")
      (node (ref "U3") (pin "AE9") (pinfunction "DRAM_D24_AE9") (pintype "bidirectional"))
      (node (ref "U7") (pin "E3") (pinfunction "DQ0_E3") (pintype "bidirectional"))
    )
    (net (code "53") (name "/DRAM_D25") (class "Default")
      (node (ref "U3") (pin "Y10") (pinfunction "DRAM_D25_Y10") (pintype "bidirectional"))
      (node (ref "U7") (pin "F8") (pinfunction "DQ3_F8") (pintype "bidirectional"))
    )
    (net (code "54") (name "/DRAM_D26") (class "Default")
      (node (ref "U3") (pin "AE11") (pinfunction "DRAM_D26_AE11") (pintype "bidirectional"))
      (node (ref "U7") (pin "H3") (pinfunction "DQ4_H3") (pintype "bidirectional"))
    )
    (net (code "55") (name "/DRAM_D27") (class "Default")
      (node (ref "U3") (pin "AB11") (pinfunction "DRAM_D27_AB11") (pintype "bidirectional"))
      (node (ref "U7") (pin "G2") (pinfunction "DQ6_G2") (pintype "bidirectional"))
    )
    (net (code "56") (name "/DRAM_D28") (class "Default")
      (node (ref "U3") (pin "AC9") (pinfunction "DRAM_D28_AC9") (pintype "bidirectional"))
      (node (ref "U7") (pin "F7") (pinfunction "DQ1_F7") (pintype "bidirectional"))
    )
    (net (code "57") (name "/DRAM_D29") (class "Default")
      (node (ref "U3") (pin "AD9") (pinfunction "DRAM_D29_AD9") (pintype "bidirectional"))
      (node (ref "U7") (pin "F2") (pinfunction "DQ2_F2") (pintype "bidirectional"))
    )
    (net (code "58") (name "/DRAM_D30") (class "Default")
      (node (ref "U3") (pin "AD11") (pinfunction "DRAM_D30_AD11") (pintype "bidirectional"))
      (node (ref "U7") (pin "H7") (pinfunction "DQ7_H7") (pintype "bidirectional"))
    )
    (net (code "59") (name "/DRAM_D31") (class "Default")
      (node (ref "U3") (pin "AC11") (pinfunction "DRAM_D31_AC11") (pintype "bidirectional"))
      (node (ref "U7") (pin "H8") (pinfunction "DQ5_H8") (pintype "bidirectional"))
    )
    (net (code "60") (name "/DRAM_D32") (class "Default")
      (node (ref "U10") (pin "E3") (pinfunction "DQ0_E3") (pintype "bidirectional"))
      (node (ref "U3") (pin "AA17") (pinfunction "DRAM_D32_AA17") (pintype "bidirectional"))
    )
    (net (code "61") (name "/DRAM_D33") (class "Default")
      (node (ref "U10") (pin "G2") (pinfunction "DQ6_G2") (pintype "bidirectional"))
      (node (ref "U3") (pin "AA18") (pinfunction "DRAM_D33_AA18") (pintype "bidirectional"))
    )
    (net (code "62") (name "/DRAM_D34") (class "Default")
      (node (ref "U10") (pin "H8") (pinfunction "DQ5_H8") (pintype "bidirectional"))
      (node (ref "U3") (pin "AC18") (pinfunction "DRAM_D34_AC18") (pintype "bidirectional"))
    )
    (net (code "63") (name "/DRAM_D35") (class "Default")
      (node (ref "U10") (pin "F2") (pinfunction "DQ2_F2") (pintype "bidirectional"))
      (node (ref "U3") (pin "AE19") (pinfunction "DRAM_D35_AE19") (pintype "bidirectional"))
    )
    (net (code "64") (name "/DRAM_D36") (class "Default")
      (node (ref "U10") (pin "H3") (pinfunction "DQ4_H3") (pintype "bidirectional"))
      (node (ref "U3") (pin "Y17") (pinfunction "DRAM_D36_Y17") (pintype "bidirectional"))
    )
    (net (code "65") (name "/DRAM_D37") (class "Default")
      (node (ref "U10") (pin "H7") (pinfunction "DQ7_H7") (pintype "bidirectional"))
      (node (ref "U3") (pin "Y18") (pinfunction "DRAM_D37_Y18") (pintype "bidirectional"))
    )
    (net (code "66") (name "/DRAM_D38") (class "Default")
      (node (ref "U10") (pin "F8") (pinfunction "DQ3_F8") (pintype "bidirectional"))
      (node (ref "U3") (pin "AB19") (pinfunction "DRAM_D38_AB19") (pintype "bidirectional"))
    )
    (net (code "67") (name "/DRAM_D39") (class "Default")
      (node (ref "U10") (pin "F7") (pinfunction "DQ1_F7") (pintype "bidirectional"))
      (node (ref "U3") (pin "AC19") (pinfunction "DRAM_D39_AC19") (pintype "bidirectional"))
    )
    (net (code "68") (name "/DRAM_D40") (class "Default")
      (node (ref "U10") (pin "D7") (pinfunction "DQ8_D7") (pintype "bidirectional"))
      (node (ref "U3") (pin "Y19") (pinfunction "DRAM_D40_Y19") (pintype "bidirectional"))
    )
    (net (code "69") (name "/DRAM_D41") (class "Default")
      (node (ref "U10") (pin "A3") (pinfunction "DQ15_A3") (pintype "bidirectional"))
      (node (ref "U3") (pin "AB20") (pinfunction "DRAM_D41_AB20") (pintype "bidirectional"))
    )
    (net (code "70") (name "/DRAM_D42") (class "Default")
      (node (ref "U10") (pin "C8") (pinfunction "DQ10_C8") (pintype "bidirectional"))
      (node (ref "U3") (pin "AB21") (pinfunction "DRAM_D42_AB21") (pintype "bidirectional"))
    )
    (net (code "71") (name "/DRAM_D43") (class "Default")
      (node (ref "U10") (pin "C3") (pinfunction "DQ9_C3") (pintype "bidirectional"))
      (node (ref "U3") (pin "AD21") (pinfunction "DRAM_D43_AD21") (pintype "bidirectional"))
    )
    (net (code "72") (name "/DRAM_D44") (class "Default")
      (node (ref "U10") (pin "A2") (pinfunction "DQ13_A2") (pintype "bidirectional"))
      (node (ref "U3") (pin "Y20") (pinfunction "DRAM_D44_Y20") (pintype "bidirectional"))
    )
    (net (code "73") (name "/DRAM_D45") (class "Default")
      (node (ref "U10") (pin "B8") (pinfunction "DQ14_B8") (pintype "bidirectional"))
      (node (ref "U3") (pin "AA20") (pinfunction "DRAM_D45_AA20") (pintype "bidirectional"))
    )
    (net (code "74") (name "/DRAM_D46") (class "Default")
      (node (ref "U10") (pin "C2") (pinfunction "DQ11_C2") (pintype "bidirectional"))
      (node (ref "U3") (pin "AE21") (pinfunction "DRAM_D46_AE21") (pintype "bidirectional"))
    )
    (net (code "75") (name "/DRAM_D47") (class "Default")
      (node (ref "U10") (pin "A7") (pinfunction "DQ12_A7") (pintype "bidirectional"))
      (node (ref "U3") (pin "AC21") (pinfunction "DRAM_D47_AC21") (pintype "bidirectional"))
    )
    (net (code "76") (name "/DRAM_D48") (class "Default")
      (node (ref "U3") (pin "AC22") (pinfunction "DRAM_D48_AC22") (pintype "bidirectional"))
      (node (ref "U9") (pin "D7") (pinfunction "DQ8_D7") (pintype "bidirectional"))
    )
    (net (code "77") (name "/DRAM_D49") (class "Default")
      (node (ref "U3") (pin "AE22") (pinfunction "DRAM_D49_AE22") (pintype "bidirectional"))
      (node (ref "U9") (pin "A7") (pinfunction "DQ12_A7") (pintype "bidirectional"))
    )
    (net (code "78") (name "/DRAM_D50") (class "Default")
      (node (ref "U3") (pin "AE24") (pinfunction "DRAM_D50_AE24") (pintype "bidirectional"))
      (node (ref "U9") (pin "A3") (pinfunction "DQ15_A3") (pintype "bidirectional"))
    )
    (net (code "79") (name "/DRAM_D51") (class "Default")
      (node (ref "U3") (pin "AC24") (pinfunction "DRAM_D51_AC24") (pintype "bidirectional"))
      (node (ref "U9") (pin "C3") (pinfunction "DQ9_C3") (pintype "bidirectional"))
    )
    (net (code "80") (name "/DRAM_D52") (class "Default")
      (node (ref "U3") (pin "AB22") (pinfunction "DRAM_D52_AB22") (pintype "bidirectional"))
      (node (ref "U9") (pin "B8") (pinfunction "DQ14_B8") (pintype "bidirectional"))
    )
    (net (code "81") (name "/DRAM_D53") (class "Default")
      (node (ref "U3") (pin "AC23") (pinfunction "DRAM_D53_AC23") (pintype "bidirectional"))
      (node (ref "U9") (pin "C8") (pinfunction "DQ10_C8") (pintype "bidirectional"))
    )
    (net (code "82") (name "/DRAM_D54") (class "Default")
      (node (ref "U3") (pin "AD25") (pinfunction "DRAM_D54_AD25") (pintype "bidirectional"))
      (node (ref "U9") (pin "A2") (pinfunction "DQ13_A2") (pintype "bidirectional"))
    )
    (net (code "83") (name "/DRAM_D55") (class "Default")
      (node (ref "U3") (pin "AC25") (pinfunction "DRAM_D55_AC25") (pintype "bidirectional"))
      (node (ref "U9") (pin "C2") (pinfunction "DQ11_C2") (pintype "bidirectional"))
    )
    (net (code "84") (name "/DRAM_D56") (class "Default")
      (node (ref "U3") (pin "AB25") (pinfunction "DRAM_D56_AB25") (pintype "bidirectional"))
      (node (ref "U9") (pin "E3") (pinfunction "DQ0_E3") (pintype "bidirectional"))
    )
    (net (code "85") (name "/DRAM_D57") (class "Default")
      (node (ref "U3") (pin "AA21") (pinfunction "DRAM_D57_AA21") (pintype "bidirectional"))
      (node (ref "U9") (pin "F8") (pinfunction "DQ3_F8") (pintype "bidirectional"))
    )
    (net (code "86") (name "/DRAM_D58") (class "Default")
      (node (ref "U3") (pin "Y25") (pinfunction "DRAM_D58_Y25") (pintype "bidirectional"))
      (node (ref "U9") (pin "G2") (pinfunction "DQ6_G2") (pintype "bidirectional"))
    )
    (net (code "87") (name "/DRAM_D59") (class "Default")
      (node (ref "U3") (pin "Y22") (pinfunction "DRAM_D59_Y22") (pintype "bidirectional"))
      (node (ref "U9") (pin "H8") (pinfunction "DQ5_H8") (pintype "bidirectional"))
    )
    (net (code "88") (name "/DRAM_D60") (class "Default")
      (node (ref "U3") (pin "AB23") (pinfunction "DRAM_D60_AB23") (pintype "bidirectional"))
      (node (ref "U9") (pin "F7") (pinfunction "DQ1_F7") (pintype "bidirectional"))
    )
    (net (code "89") (name "/DRAM_D61") (class "Default")
      (node (ref "U3") (pin "AA23") (pinfunction "DRAM_D61_AA23") (pintype "bidirectional"))
      (node (ref "U9") (pin "H7") (pinfunction "DQ7_H7") (pintype "bidirectional"))
    )
    (net (code "90") (name "/DRAM_D62") (class "Default")
      (node (ref "U3") (pin "Y23") (pinfunction "DRAM_D62_Y23") (pintype "bidirectional"))
      (node (ref "U9") (pin "F2") (pinfunction "DQ2_F2") (pintype "bidirectional"))
    )
    (net (code "91") (name "/DRAM_D63") (class "Default")
      (node (ref "U3") (pin "W25") (pinfunction "DRAM_D63_W25") (pintype "bidirectional"))
      (node (ref "U9") (pin "H3") (pinfunction "DQ4_H3") (pintype "bidirectional"))
    )
    (net (code "92") (name "/DRAM_DQM0") (class "Default")
      (node (ref "U3") (pin "AC3") (pinfunction "DRAM_DQM0_AC3") (pintype "output"))
      (node (ref "U8") (pin "E7") (pinfunction "LDM_E7") (pintype "input"))
    )
    (net (code "93") (name "/DRAM_DQM1") (class "Default")
      (node (ref "U3") (pin "AC6") (pinfunction "DRAM_DQM1_AC6") (pintype "output"))
      (node (ref "U8") (pin "D3") (pinfunction "UDM_D3") (pintype "input"))
    )
    (net (code "94") (name "/DRAM_DQM2") (class "Default")
      (node (ref "U3") (pin "AB8") (pinfunction "DRAM_DQM2_AB8") (pintype "output"))
      (node (ref "U7") (pin "D3") (pinfunction "UDM_D3") (pintype "input"))
    )
    (net (code "95") (name "/DRAM_DQM3") (class "Default")
      (node (ref "U3") (pin "AE10") (pinfunction "DRAM_DQM3_AE10") (pintype "output"))
      (node (ref "U7") (pin "E7") (pinfunction "LDM_E7") (pintype "input"))
    )
    (net (code "96") (name "/DRAM_DQM4") (class "Default")
      (node (ref "U10") (pin "E7") (pinfunction "LDM_E7") (pintype "input"))
      (node (ref "U3") (pin "AB18") (pinfunction "DRAM_DQM4_AB18") (pintype "output"))
    )
    (net (code "97") (name "/DRAM_DQM5") (class "Default")
      (node (ref "U10") (pin "D3") (pinfunction "UDM_D3") (pintype "input"))
      (node (ref "U3") (pin "AC20") (pinfunction "DRAM_DQM5_AC20") (pintype "output"))
    )
    (net (code "98") (name "/DRAM_DQM6") (class "Default")
      (node (ref "U3") (pin "AD24") (pinfunction "DRAM_DQM6_AD24") (pintype "output"))
      (node (ref "U9") (pin "D3") (pinfunction "UDM_D3") (pintype "input"))
    )
    (net (code "99") (name "/DRAM_DQM7") (class "Default")
      (node (ref "U3") (pin "Y21") (pinfunction "DRAM_DQM7_Y21") (pintype "output"))
      (node (ref "U9") (pin "E7") (pinfunction "LDM_E7") (pintype "input"))
    )
    (net (code "101") (name "/DRAM_RAS_B") (class "Default")
      (node (ref "U10") (pin "J3") (pinfunction "~{RAS}_J3") (pintype "input"))
      (node (ref "U3") (pin "AB15") (pinfunction "DRAM_RAS_AB15") (pintype "output"))
      (node (ref "U7") (pin "J3") (pinfunction "~{RAS}_J3") (pintype "input"))
      (node (ref "U8") (pin "J3") (pinfunction "~{RAS}_J3") (pintype "input"))
      (node (ref "U9") (pin "J3") (pinfunction "~{RAS}_J3") (pintype "input"))
    )
    (net (code "102") (name "/DRAM_RESET_B") (class "Default")
      (node (ref "R38") (pin "1") (pinfunction "1_1") (pintype "passive"))
      (node (ref "U10") (pin "T2") (pinfunction "~{RESET}_T2") (pintype "input"))
      (node (ref "U3") (pin "Y6") (pinfunction "DRAM_RESET_Y6") (pintype "output"))
      (node (ref "U7") (pin "T2") (pinfunction "~{RESET}_T2") (pintype "input"))
      (node (ref "U8") (pin "T2") (pinfunction "~{RESET}_T2") (pintype "input"))
      (node (ref "U9") (pin "T2") (pinfunction "~{RESET}_T2") (pintype "input"))
    )
    (net (code "103") (name "/DRAM_SDBA0") (class "Default")
      (node (ref "U10") (pin "M2") (pinfunction "BA0_M2") (pintype "input"))
      (node (ref "U3") (pin "AC15") (pinfunction "DRAM_SDBA0_AC15") (pintype "output"))
      (node (ref "U7") (pin "M2") (pinfunction "BA0_M2") (pintype "input"))
      (node (ref "U8") (pin "M2") (pinfunction "BA0_M2") (pintype "input"))
      (node (ref "U9") (pin "M2") (pinfunction "BA0_M2") (pintype "input"))
    )
    (net (code "104") (name "/DRAM_SDBA1") (class "Default")
      (node (ref "U10") (pin "N8") (pinfunction "BA1_N8") (pintype "input"))
      (node (ref "U3") (pin "Y15") (pinfunction "DRAM_SDBA1_Y15") (pintype "output"))
      (node (ref "U7") (pin "N8") (pinfunction "BA1_N8") (pintype "input"))
      (node (ref "U8") (pin "N8") (pinfunction "BA1_N8") (pintype "input"))
      (node (ref "U9") (pin "N8") (pinfunction "BA1_N8") (pintype "input"))
    )
    (net (code "105") (name "/DRAM_SDBA2") (class "Default")
      (node (ref "U10") (pin "M3") (pinfunction "BA2_M3") (pintype "input"))
      (node (ref "U3") (pin "AB12") (pinfunction "DRAM_SDBA2_AB12") (pintype "output"))
      (node (ref "U7") (pin "M3") (pinfunction "BA2_M3") (pintype "input"))
      (node (ref "U8") (pin "M3") (pinfunction "BA2_M3") (pintype "input"))
      (node (ref "U9") (pin "M3") (pinfunction "BA2_M3") (pintype "input"))
    )
    (net (code "106") (name "/DRAM_SDCKE0") (class "Default")
      (node (ref "R37") (pin "1") (pinfunction "1_1") (pintype "passive"))
      (node (ref "U10") (pin "K9") (pinfunction "CKE_K9") (pintype "input"))
      (node (ref "U3") (pin "Y11") (pinfunction "DRAM_SDCKE0_Y11") (pintype "output"))
      (node (ref "U7") (pin "K9") (pinfunction "CKE_K9") (pintype "input"))
      (node (ref "U8") (pin "K9") (pinfunction "CKE_K9") (pintype "input"))
      (node (ref "U9") (pin "K9") (pinfunction "CKE_K9") (pintype "input"))
    )
    (net (code "107") (name "/DRAM_SDCLK0") (class "Default")
      (node (ref "R33") (pin "1") (pinfunction "1_1") (pintype "passive"))
      (node (ref "SH1") (pin "2") (pinfunction "2_2") (pintype "passive"))
      (node (ref "U10") (pin "J7") (pinfunction "CK_J7") (pintype "input"))
      (node (ref "U9") (pin "J7") (pinfunction "CK_J7") (pintype "input"))
    )
    (net (code "108") (name "/DRAM_SDCLK0_B") (class "Default")
      (node (ref "R33") (pin "2") (pinfunction "2_2") (pintype "passive"))
      (node (ref "SH2") (pin "2") (pinfunction "2_2") (pintype "passive"))
      (node (ref "U10") (pin "K7") (pinfunction "~{CK}_K7") (pintype "input"))
      (node (ref "U9") (pin "K7") (pinfunction "~{CK}_K7") (pintype "input"))
    )
    (net (code "109") (name "/DRAM_SDCLK1") (class "Default")
      (node (ref "R34") (pin "1") (pinfunction "1_1") (pintype "passive"))
      (node (ref "SH3") (pin "2") (pinfunction "2_2") (pintype "passive"))
      (node (ref "U7") (pin "J7") (pinfunction "CK_J7") (pintype "input"))
      (node (ref "U8") (pin "J7") (pinfunction "CK_J7") (pintype "input"))
    )
    (net (code "110") (name "/DRAM_SDCLK1_B") (class "Default")
      (node (ref "R34") (pin "2") (pinfunction "2_2") (pintype "passive"))
      (node (ref "SH4") (pin "2") (pinfunction "2_2") (pintype "passive"))
      (node (ref "U7") (pin "K7") (pinfunction "~{CK}_K7") (pintype "input"))
      (node (ref "U8") (pin "K7") (pinfunction "~{CK}_K7") (pintype "input"))
    )
    (net (code "111") (name "/DRAM_SDODT0") (class "Default")
      (node (ref "U10") (pin "K1") (pinfunction "ODT_K1") (pintype "input"))
      (node (ref "U3") (pin "AC16") (pinfunction "DRAM_SDODT0_AC16") (pintype "output"))
      (node (ref "U7") (pin "K1") (pinfunction "ODT_K1") (pintype "input"))
      (node (ref "U8") (pin "K1") (pinfunction "ODT_K1") (pintype "input"))
      (node (ref "U9") (pin "K1") (pinfunction "ODT_K1") (pintype "input"))
    )
    (net (code "112") (name "/DRAM_SDQS0") (class "Default")
      (node (ref "U3") (pin "AE3") (pinfunction "DRAM_SDQS0_AE3") (pintype "bidirectional"))
      (node (ref "U8") (pin "F3") (pinfunction "LDQS_F3") (pintype "bidirectional"))
    )
    (net (code "113") (name "/DRAM_SDQS0_B") (class "Default")
      (node (ref "U3") (pin "AD3") (pinfunction "~{DRAM_SDQS0}_AD3") (pintype "bidirectional"))
      (node (ref "U8") (pin "G3") (pinfunction "~{LDQS}_G3") (pintype "bidirectional"))
    )
    (net (code "114") (name "/DRAM_SDQS1") (class "Default")
      (node (ref "U3") (pin "AD6") (pinfunction "DRAM_SDQS1_AD6") (pintype "bidirectional"))
      (node (ref "U8") (pin "C7") (pinfunction "UDQS_C7") (pintype "bidirectional"))
    )
    (net (code "115") (name "/DRAM_SDQS1_B") (class "Default")
      (node (ref "U3") (pin "AE6") (pinfunction "~{DRAM_SDQS1}_AE6") (pintype "bidirectional"))
      (node (ref "U8") (pin "B7") (pinfunction "~{UDQS}_B7") (pintype "bidirectional"))
    )
    (net (code "116") (name "/DRAM_SDQS2") (class "Default")
      (node (ref "U3") (pin "AD8") (pinfunction "DRAM_SDQS2_AD8") (pintype "bidirectional"))
      (node (ref "U7") (pin "C7") (pinfunction "UDQS_C7") (pintype "bidirectional"))
    )
    (net (code "117") (name "/DRAM_SDQS2_B") (class "Default")
      (node (ref "U3") (pin "AE8") (pinfunction "~{DRAM_SDQS2}_AE8") (pintype "bidirectional"))
      (node (ref "U7") (pin "B7") (pinfunction "~{UDQS}_B7") (pintype "bidirectional"))
    )
    (net (code "118") (name "/DRAM_SDQS3") (class "Default")
      (node (ref "U3") (pin "AC10") (pinfunction "DRAM_SDQS3_AC10") (pintype "bidirectional"))
      (node (ref "U7") (pin "F3") (pinfunction "LDQS_F3") (pintype "bidirectional"))
    )
    (net (code "119") (name "/DRAM_SDQS3_B") (class "Default")
      (node (ref "U3") (pin "AB10") (pinfunction "~{DRAM_SDQS3}_AB10") (pintype "bidirectional"))
      (node (ref "U7") (pin "G3") (pinfunction "~{LDQS}_G3") (pintype "bidirectional"))
    )
    (net (code "120") (name "/DRAM_SDQS4") (class "Default")
      (node (ref "U10") (pin "F3") (pinfunction "LDQS_F3") (pintype "bidirectional"))
      (node (ref "U3") (pin "AD18") (pinfunction "DRAM_SDQS4_AD18") (pintype "bidirectional"))
    )
    (net (code "121") (name "/DRAM_SDQS4_B") (class "Default")
      (node (ref "U10") (pin "G3") (pinfunction "~{LDQS}_G3") (pintype "bidirectional"))
      (node (ref "U3") (pin "AE18") (pinfunction "~{DRAM_SDQS4}_AE18") (pintype "bidirectional"))
    )
    (net (code "122") (name "/DRAM_SDQS5") (class "Default")
      (node (ref "U10") (pin "C7") (pinfunction "UDQS_C7") (pintype "bidirectional"))
      (node (ref "U3") (pin "AD20") (pinfunction "DRAM_SDQS5_AD20") (pintype "bidirectional"))
    )
    (net (code "123") (name "/DRAM_SDQS5_B") (class "Default")
      (node (ref "U10") (pin "B7") (pinfunction "~{UDQS}_B7") (pintype "bidirectional"))
      (node (ref "U3") (pin "AE20") (pinfunction "~{DRAM_SDQS5}_AE20") (pintype "bidirectional"))
    )
    (net (code "124") (name "/DRAM_SDQS6") (class "Default")
      (node (ref "U3") (pin "AD23") (pinfunction "DRAM_SDQS6_AD23") (pintype "bidirectional"))
      (node (ref "U9") (pin "C7") (pinfunction "UDQS_C7") (pintype "bidirectional"))
    )
    (net (code "125") (name "/DRAM_SDQS6_B") (class "Default")
      (node (ref "U3") (pin "AE23") (pinfunction "~{DRAM_SDQS6}_AE23") (pintype "bidirectional"))
      (node (ref "U9") (pin "B7") (pinfunction "~{UDQS}_B7") (pintype "bidirectional"))
    )
    (net (code "126") (name "/DRAM_SDQS7") (class "Default")
      (node (ref "U3") (pin "AA25") (pinfunction "DRAM_SDQS7_AA25") (pintype "bidirectional"))
      (node (ref "U9") (pin "F3") (pinfunction "LDQS_F3") (pintype "bidirectional"))
    )
    (net (code "127") (name "/DRAM_SDQS7_B") (class "Default")
      (node (ref "U3") (pin "AA24") (pinfunction "~{DRAM_SDQS7}_AA24") (pintype "bidirectional"))
      (node (ref "U9") (pin "G3") (pinfunction "~{LDQS}_G3") (pintype "bidirectional"))
    )
    (net (code "128") (name "/DRAM_WE_B") (class "Default")
      (node (ref "U10") (pin "L3") (pinfunction "~{WE}_L3") (pintype "input"))
      (node (ref "U3") (pin "AB16") (pinfunction "DRAM_SDWE_AB16") (pintype "output"))
      (node (ref "U7") (pin "L3") (pinfunction "~{WE}_L3") (pintype "input"))
      (node (ref "U8") (pin "L3") (pinfunction "~{WE}_L3") (pintype "input"))
      (node (ref "U9") (pin "L3") (pinfunction "~{WE}_L3") (pintype "input"))
    )
    (net (code "129") (name "/ZQPAD") (class "Default")
      (node (ref "R40") (pin "1") (pinfunction "1_1") (pintype "passive"))
      (node (ref "U3") (pin "AE17") (pinfunction "ZQPAD_AE17") (pintype "input"))
    )
    (net (code "130") (name "GND") (class "Default")
      (node (ref "C126") (pin "2") (pinfunction "2_2") (pintype "passive"))
      (node (ref "C127") (pin "2") (pinfunction "2_2") (pintype "passive"))
      (node (ref "C128") (pin "2") (pinfunction "2_2") (pintype "passive"))
      (node (ref "C129") (pin "2") (pinfunction "2_2") (pintype "passive"))
      (node (ref "C130") (pin "2") (pinfunction "2_2") (pintype "passive"))
      (node (ref "C131") (pin "2") (pinfunction "2_2") (pintype "passive"))
      (node (ref "C132") (pin "2") (pinfunction "2_2") (pintype "passive"))
      (node (ref "C133") (pin "2") (pinfunction "2_2") (pintype "passive"))
      (node (ref "C134") (pin "2") (pinfunction "2_2") (pintype "passive"))
      (node (ref "C135") (pin "2") (pinfunction "2_2") (pintype "passive"))
      (node (ref "C136") (pin "2") (pinfunction "2_2") (pintype "passive"))
      (node (ref "C137") (pin "2") (pinfunction "2_2") (pintype "passive"))
      (node (ref "C138") (pin "2") (pinfunction "2_2") (pintype "passive"))
      (node (ref "C139") (pin "2") (pinfunction "2_2") (pintype "passive"))
      (node (ref "C140") (pin "2") (pinfunction "2_2") (pintype "passive"))
      (node (ref "C141") (pin "2") (pinfunction "2_2") (pintype "passive"))
      (node (ref "C142") (pin "2") (pinfunction "2_2") (pintype "passive"))
      (node (ref "C143") (pin "2") (pinfunction "2_2") (pintype "passive"))
      (node (ref "C144") (pin "2") (pinfunction "2_2") (pintype "passive"))
      (node (ref "C145") (pin "2") (pinfunction "2_2") (pintype "passive"))
      (node (ref "C146") (pin "2") (pinfunction "2_2") (pintype "passive"))
      (node (ref "C147") (pin "2") (pinfunction "2_2") (pintype "passive"))
      (node (ref "C148") (pin "2") (pinfunction "2_2") (pintype "passive"))
      (node (ref "C149") (pin "2") (pinfunction "2_2") (pintype "passive"))
      (node (ref "C150") (pin "2") (pinfunction "2_2") (pintype "passive"))
      (node (ref "C151") (pin "2") (pinfunction "2_2") (pintype "passive"))
      (node (ref "C152") (pin "2") (pinfunction "2_2") (pintype "passive"))
      (node (ref "C153") (pin "2") (pinfunction "2_2") (pintype "passive"))
      (node (ref "C154") (pin "2") (pinfunction "2_2") (pintype "passive"))
      (node (ref "C155") (pin "2") (pinfunction "2_2") (pintype "passive"))
      (node (ref "C156") (pin "2") (pinfunction "2_2") (pintype "passive"))
      (node (ref "C157") (pin "2") (pinfunction "2_2") (pintype "passive"))
      (node (ref "C158") (pin "2") (pinfunction "2_2") (pintype "passive"))
      (node (ref "C159") (pin "2") (pinfunction "2_2") (pintype "passive"))
      (node (ref "C160") (pin "2") (pinfunction "2_2") (pintype "passive"))
      (node (ref "C161") (pin "2") (pinfunction "2_2") (pintype "passive"))
      (node (ref "C162") (pin "2") (pinfunction "2_2") (pintype "passive"))
      (node (ref "C163") (pin "2") (pinfunction "2_2") (pintype "passive"))
      (node (ref "C164") (pin "2") (pinfunction "2_2") (pintype "passive"))
      (node (ref "C165") (pin "2") (pinfunction "2_2") (pintype "passive"))
      (node (ref "C166") (pin "2") (pinfunction "2_2") (pintype "passive"))
      (node (ref "C167") (pin "2") (pinfunction "2_2") (pintype "passive"))
      (node (ref "C168") (pin "2") (pinfunction "2_2") (pintype "passive"))
      (node (ref "C169") (pin "2") (pinfunction "2_2") (pintype "passive"))
      (node (ref "C170") (pin "2") (pinfunction "2_2") (pintype "passive"))
      (node (ref "C171") (pin "2") (pinfunction "2_2") (pintype "passive"))
      (node (ref "C172") (pin "2") (pinfunction "2_2") (pintype "passive"))
      (node (ref "C173") (pin "2") (pinfunction "2_2") (pintype "passive"))
      (node (ref "C174") (pin "2") (pinfunction "2_2") (pintype "passive"))
      (node (ref "C175") (pin "2") (pinfunction "2_2") (pintype "passive"))
      (node (ref "C176") (pin "2") (pinfunction "2_2") (pintype "passive"))
      (node (ref "C177") (pin "2") (pinfunction "2_2") (pintype "passive"))
      (node (ref "C178") (pin "2") (pinfunction "2_2") (pintype "passive"))
      (node (ref "C179") (pin "2") (pinfunction "2_2") (pintype "passive"))
      (node (ref "C180") (pin "2") (pinfunction "2_2") (pintype "passive"))
      (node (ref "C181") (pin "2") (pinfunction "2_2") (pintype "passive"))
      (node (ref "C182") (pin "2") (pinfunction "2_2") (pintype "passive"))
      (node (ref "C183") (pin "2") (pinfunction "2_2") (pintype "passive"))
      (node (ref "C184") (pin "2") (pinfunction "2_2") (pintype "passive"))
      (node (ref "C185") (pin "2") (pinfunction "2_2") (pintype "passive"))
      (node (ref "C186") (pin "2") (pinfunction "2_2") (pintype "passive"))
      (node (ref "C187") (pin "2") (pinfunction "2_2") (pintype "passive"))
      (node (ref "C188") (pin "2") (pinfunction "2_2") (pintype "passive"))
      (node (ref "C189") (pin "2") (pinfunction "2_2") (pintype "passive"))
      (node (ref "C190") (pin "2") (pinfunction "2_2") (pintype "passive"))
      (node (ref "C191") (pin "2") (pinfunction "2_2") (pintype "passive"))
      (node (ref "R35") (pin "1") (pinfunction "1_1") (pintype "passive"))
      (node (ref "R36") (pin "1") (pinfunction "1_1") (pintype "passive"))
      (node (ref "R37") (pin "2") (pinfunction "2_2") (pintype "passive"))
      (node (ref "R38") (pin "2") (pinfunction "2_2") (pintype "passive"))
      (node (ref "R39") (pin "1") (pinfunction "1_1") (pintype "passive"))
      (node (ref "R40") (pin "2") (pinfunction "2_2") (pintype "passive"))
      (node (ref "R41") (pin "1") (pinfunction "1_1") (pintype "passive"))
      (node (ref "U10") (pin "A9") (pinfunction "VSS1_A9") (pintype "power_in"))
      (node (ref "U10") (pin "B1") (pinfunction "VSSQ1_B1") (pintype "power_in"))
      (node (ref "U10") (pin "B3") (pinfunction "VSS2_B3") (pintype "power_in"))
      (node (ref "U10") (pin "B9") (pinfunction "VSSQ2_B9") (pintype "power_in"))
      (node (ref "U10") (pin "D1") (pinfunction "VSSQ3_D1") (pintype "power_in"))
      (node (ref "U10") (pin "D8") (pinfunction "VSSQ4_D8") (pintype "power_in"))
      (node (ref "U10") (pin "E1") (pinfunction "VSS3_E1") (pintype "power_in"))
      (node (ref "U10") (pin "E2") (pinfunction "VSSQ5_E2") (pintype "power_in"))
      (node (ref "U10") (pin "E8") (pinfunction "VSSQ6_E8") (pintype "power_in"))
      (node (ref "U10") (pin "F9") (pinfunction "VSSQ7_F9") (pintype "power_in"))
      (node (ref "U10") (pin "G1") (pinfunction "VSSQ8_G1") (pintype "power_in"))
      (node (ref "U10") (pin "G8") (pinfunction "VSS4_G8") (pintype "power_in"))
      (node (ref "U10") (pin "G9") (pinfunction "VSSQ9_G9") (pintype "power_in"))
      (node (ref "U10") (pin "J2") (pinfunction "VSS5_J2") (pintype "power_in"))
      (node (ref "U10") (pin "J8") (pinfunction "VSS6_J8") (pintype "power_in"))
      (node (ref "U10") (pin "M1") (pinfunction "VSS7_M1") (pintype "power_in"))
      (node (ref "U10") (pin "M9") (pinfunction "VSS8_M9") (pintype "power_in"))
      (node (ref "U10") (pin "P1") (pinfunction "VSS9_P1") (pintype "power_in"))
      (node (ref "U10") (pin "P9") (pinfunction "VSS10_P9") (pintype "power_in"))
      (node (ref "U10") (pin "T1") (pinfunction "VSS11_T1") (pintype "power_in"))
      (node (ref "U10") (pin "T9") (pinfunction "VSS12_T9") (pintype "power_in"))
      (node (ref "U7") (pin "A9") (pinfunction "VSS1_A9") (pintype "power_in"))
      (node (ref "U7") (pin "B1") (pinfunction "VSSQ1_B1") (pintype "power_in"))
      (node (ref "U7") (pin "B3") (pinfunction "VSS2_B3") (pintype "power_in"))
      (node (ref "U7") (pin "B9") (pinfunction "VSSQ2_B9") (pintype "power_in"))
      (node (ref "U7") (pin "D1") (pinfunction "VSSQ3_D1") (pintype "power_in"))
      (node (ref "U7") (pin "D8") (pinfunction "VSSQ4_D8") (pintype "power_in"))
      (node (ref "U7") (pin "E1") (pinfunction "VSS3_E1") (pintype "power_in"))
      (node (ref "U7") (pin "E2") (pinfunction "VSSQ5_E2") (pintype "power_in"))
      (node (ref "U7") (pin "E8") (pinfunction "VSSQ6_E8") (pintype "power_in"))
      (node (ref "U7") (pin "F9") (pinfunction "VSSQ7_F9") (pintype "power_in"))
      (node (ref "U7") (pin "G1") (pinfunction "VSSQ8_G1") (pintype "power_in"))
      (node (ref "U7") (pin "G8") (pinfunction "VSS4_G8") (pintype "power_in"))
      (node (ref "U7") (pin "G9") (pinfunction "VSSQ9_G9") (pintype "power_in"))
      (node (ref "U7") (pin "J2") (pinfunction "VSS5_J2") (pintype "power_in"))
      (node (ref "U7") (pin "J8") (pinfunction "VSS6_J8") (pintype "power_in"))
      (node (ref "U7") (pin "M1") (pinfunction "VSS7_M1") (pintype "power_in"))
      (node (ref "U7") (pin "M9") (pinfunction "VSS8_M9") (pintype "power_in"))
      (node (ref "U7") (pin "P1") (pinfunction "VSS9_P1") (pintype "power_in"))
      (node (ref "U7") (pin "P9") (pinfunction "VSS10_P9") (pintype "power_in"))
      (node (ref "U7") (pin "T1") (pinfunction "VSS11_T1") (pintype "power_in"))
      (node (ref "U7") (pin "T9") (pinfunction "VSS12_T9") (pintype "power_in"))
      (node (ref "U8") (pin "A9") (pinfunction "VSS1_A9") (pintype "power_in"))
      (node (ref "U8") (pin "B1") (pinfunction "VSSQ1_B1") (pintype "power_in"))
      (node (ref "U8") (pin "B3") (pinfunction "VSS2_B3") (pintype "power_in"))
      (node (ref "U8") (pin "B9") (pinfunction "VSSQ2_B9") (pintype "power_in"))
      (node (ref "U8") (pin "D1") (pinfunction "VSSQ3_D1") (pintype "power_in"))
      (node (ref "U8") (pin "D8") (pinfunction "VSSQ4_D8") (pintype "power_in"))
      (node (ref "U8") (pin "E1") (pinfunction "VSS3_E1") (pintype "power_in"))
      (node (ref "U8") (pin "E2") (pinfunction "VSSQ5_E2") (pintype "power_in"))
      (node (ref "U8") (pin "E8") (pinfunction "VSSQ6_E8") (pintype "power_in"))
      (node (ref "U8") (pin "F9") (pinfunction "VSSQ7_F9") (pintype "power_in"))
      (node (ref "U8") (pin "G1") (pinfunction "VSSQ8_G1") (pintype "power_in"))
      (node (ref "U8") (pin "G8") (pinfunction "VSS4_G8") (pintype "power_in"))
      (node (ref "U8") (pin "G9") (pinfunction "VSSQ9_G9") (pintype "power_in"))
      (node (ref "U8") (pin "J2") (pinfunction "VSS5_J2") (pintype "power_in"))
      (node (ref "U8") (pin "J8") (pinfunction "VSS6_J8") (pintype "power_in"))
      (node (ref "U8") (pin "M1") (pinfunction "VSS7_M1") (pintype "power_in"))
      (node (ref "U8") (pin "M9") (pinfunction "VSS8_M9") (pintype "power_in"))
      (node (ref "U8") (pin "P1") (pinfunction "VSS9_P1") (pintype "power_in"))
      (node (ref "U8") (pin "P9") (pinfunction "VSS10_P9") (pintype "power_in"))
      (node (ref "U8") (pin "T1") (pinfunction "VSS11_T1") (pintype "power_in"))
      (node (ref "U8") (pin "T9") (pinfunction "VSS12_T9") (pintype "power_in"))
      (node (ref "U9") (pin "A9") (pinfunction "VSS1_A9") (pintype "power_in"))
      (node (ref "U9") (pin "B1") (pinfunction "VSSQ1_B1") (pintype "power_in"))
      (node (ref "U9") (pin "B3") (pinfunction "VSS2_B3") (pintype "power_in"))
      (node (ref "U9") (pin "B9") (pinfunction "VSSQ2_B9") (pintype "power_in"))
      (node (ref "U9") (pin "D1") (pinfunction "VSSQ3_D1") (pintype "power_in"))
      (node (ref "U9") (pin "D8") (pinfunction "VSSQ4_D8") (pintype "power_in"))
      (node (ref "U9") (pin "E1") (pinfunction "VSS3_E1") (pintype "power_in"))
      (node (ref "U9") (pin "E2") (pinfunction "VSSQ5_E2") (pintype "power_in"))
      (node (ref "U9") (pin "E8") (pinfunction "VSSQ6_E8") (pintype "power_in"))
      (node (ref "U9") (pin "F9") (pinfunction "VSSQ7_F9") (pintype "power_in"))
      (node (ref "U9") (pin "G1") (pinfunction "VSSQ8_G1") (pintype "power_in"))
      (node (ref "U9") (pin "G8") (pinfunction "VSS4_G8") (pintype "power_in"))
      (node (ref "U9") (pin "G9") (pinfunction "VSSQ9_G9") (pintype "power_in"))
      (node (ref "U9") (pin "J2") (pinfunction "VSS5_J2") (pintype "power_in"))
      (node (ref "U9") (pin "J8") (pinfunction "VSS6_J8") (pintype "power_in"))
      (node (ref "U9") (pin "M1") (pinfunction "VSS7_M1") (pintype "power_in"))
      (node (ref "U9") (pin "M9") (pinfunction "VSS8_M9") (pintype "power_in"))
      (node (ref "U9") (pin "P1") (pinfunction "VSS9_P1") (pintype "power_in"))
      (node (ref "U9") (pin "P9") (pinfunction "VSS10_P9") (pintype "power_in"))
      (node (ref "U9") (pin "T1") (pinfunction "VSS11_T1") (pintype "power_in"))
      (node (ref "U9") (pin "T9") (pinfunction "VSS12_T9") (pintype "power_in"))
    )
    (net (code "131") (name "P0V75-REFDDR") (class "Default")
      (node (ref "C126") (pin "1") (pinfunction "1_1") (pintype "passive"))
      (node (ref "C127") (pin "1") (pinfunction "1_1") (pintype "passive"))
      (node (ref "C128") (pin "1") (pinfunction "1_1") (pintype "passive"))
      (node (ref "C129") (pin "1") (pinfunction "1_1") (pintype "passive"))
      (node (ref "C130") (pin "1") (pinfunction "1_1") (pintype "passive"))
      (node (ref "C131") (pin "1") (pinfunction "1_1") (pintype "passive"))
      (node (ref "C132") (pin "1") (pinfunction "1_1") (pintype "passive"))
      (node (ref "C133") (pin "1") (pinfunction "1_1") (pintype "passive"))
      (node (ref "U10") (pin "H1") (pinfunction "VREFDQ_H1") (pintype "input"))
      (node (ref "U10") (pin "M8") (pinfunction "VREFCA_M8") (pintype "input"))
      (node (ref "U3") (pin "AC2") (pinfunction "DRAM_VREF_AC2") (pintype "power_in"))
      (node (ref "U7") (pin "H1") (pinfunction "VREFDQ_H1") (pintype "input"))
      (node (ref "U7") (pin "M8") (pinfunction "VREFCA_M8") (pintype "input"))
      (node (ref "U8") (pin "H1") (pinfunction "VREFDQ_H1") (pintype "input"))
      (node (ref "U8") (pin "M8") (pinfunction "VREFCA_M8") (pintype "input"))
      (node (ref "U9") (pin "H1") (pinfunction "VREFDQ_H1") (pintype "input"))
      (node (ref "U9") (pin "M8") (pinfunction "VREFCA_M8") (pintype "input"))
    )
    (net (code "132") (name "P1V5-DDR-SW3") (class "Default")
      (node (ref "C134") (pin "1") (pinfunction "1_1") (pintype "passive"))
      (node (ref "C135") (pin "1") (pinfunction "1_1") (pintype "passive"))
      (node (ref "C136") (pin "1") (pinfunction "1_1") (pintype "passive"))
      (node (ref "C137") (pin "1") (pinfunction "1_1") (pintype "passive"))
      (node (ref "C138") (pin "1") (pinfunction "1_1") (pintype "passive"))
      (node (ref "C139") (pin "1") (pinfunction "1_1") (pintype "passive"))
      (node (ref "C140") (pin "1") (pinfunction "1_1") (pintype "passive"))
      (node (ref "C141") (pin "1") (pinfunction "1_1") (pintype "passive"))
      (node (ref "C142") (pin "1") (pinfunction "1_1") (pintype "passive"))
      (node (ref "C143") (pin "1") (pinfunction "1_1") (pintype "passive"))
      (node (ref "C144") (pin "1") (pinfunction "1_1") (pintype "passive"))
      (node (ref "C145") (pin "1") (pinfunction "1_1") (pintype "passive"))
      (node (ref "C146") (pin "1") (pinfunction "1_1") (pintype "passive"))
      (node (ref "C147") (pin "1") (pinfunction "1_1") (pintype "passive"))
      (node (ref "C148") (pin "1") (pinfunction "1_1") (pintype "passive"))
      (node (ref "C149") (pin "1") (pinfunction "1_1") (pintype "passive"))
      (node (ref "C150") (pin "1") (pinfunction "1_1") (pintype "passive"))
      (node (ref "C151") (pin "1") (pinfunction "1_1") (pintype "passive"))
      (node (ref "C152") (pin "1") (pinfunction "1_1") (pintype "passive"))
      (node (ref "C153") (pin "1") (pinfunction "1_1") (pintype "passive"))
      (node (ref "C154") (pin "1") (pinfunction "1_1") (pintype "passive"))
      (node (ref "C155") (pin "1") (pinfunction "1_1") (pintype "passive"))
      (node (ref "C156") (pin "1") (pinfunction "1_1") (pintype "passive"))
      (node (ref "C157") (pin "1") (pinfunction "1_1") (pintype "passive"))
      (node (ref "C158") (pin "1") (pinfunction "1_1") (pintype "passive"))
      (node (ref "C159") (pin "1") (pinfunction "1_1") (pintype "passive"))
      (node (ref "C160") (pin "1") (pinfunction "1_1") (pintype "passive"))
      (node (ref "C161") (pin "1") (pinfunction "1_1") (pintype "passive"))
      (node (ref "C162") (pin "1") (pinfunction "1_1") (pintype "passive"))
      (node (ref "C163") (pin "1") (pinfunction "1_1") (pintype "passive"))
      (node (ref "C164") (pin "1") (pinfunction "1_1") (pintype "passive"))
      (node (ref "C165") (pin "1") (pinfunction "1_1") (pintype "passive"))
      (node (ref "C166") (pin "1") (pinfunction "1_1") (pintype "passive"))
      (node (ref "C167") (pin "1") (pinfunction "1_1") (pintype "passive"))
      (node (ref "C168") (pin "1") (pinfunction "1_1") (pintype "passive"))
      (node (ref "C169") (pin "1") (pinfunction "1_1") (pintype "passive"))
      (node (ref "C170") (pin "1") (pinfunction "1_1") (pintype "passive"))
      (node (ref "C171") (pin "1") (pinfunction "1_1") (pintype "passive"))
      (node (ref "C172") (pin "1") (pinfunction "1_1") (pintype "passive"))
      (node (ref "C173") (pin "1") (pinfunction "1_1") (pintype "passive"))
      (node (ref "C174") (pin "1") (pinfunction "1_1") (pintype "passive"))
      (node (ref "C175") (pin "1") (pinfunction "1_1") (pintype "passive"))
      (node (ref "C176") (pin "1") (pinfunction "1_1") (pintype "passive"))
      (node (ref "C177") (pin "1") (pinfunction "1_1") (pintype "passive"))
      (node (ref "C178") (pin "1") (pinfunction "1_1") (pintype "passive"))
      (node (ref "C179") (pin "1") (pinfunction "1_1") (pintype "passive"))
      (node (ref "C180") (pin "1") (pinfunction "1_1") (pintype "passive"))
      (node (ref "C181") (pin "1") (pinfunction "1_1") (pintype "passive"))
      (node (ref "C182") (pin "1") (pinfunction "1_1") (pintype "passive"))
      (node (ref "C183") (pin "1") (pinfunction "1_1") (pintype "passive"))
      (node (ref "C184") (pin "1") (pinfunction "1_1") (pintype "passive"))
      (node (ref "C185") (pin "1") (pinfunction "1_1") (pintype "passive"))
      (node (ref "C186") (pin "1") (pinfunction "1_1") (pintype "passive"))
      (node (ref "C187") (pin "1") (pinfunction "1_1") (pintype "passive"))
      (node (ref "C188") (pin "1") (pinfunction "1_1") (pintype "passive"))
      (node (ref "C189") (pin "1") (pinfunction "1_1") (pintype "passive"))
      (node (ref "C190") (pin "1") (pinfunction "1_1") (pintype "passive"))
      (node (ref "C191") (pin "1") (pinfunction "1_1") (pintype "passive"))
      (node (ref "U10") (pin "A1") (pinfunction "VDDQ1_A1") (pintype "power_in"))
      (node (ref "U10") (pin "A8") (pinfunction "VDDQ2_A8") (pintype "power_in"))
      (node (ref "U10") (pin "B2") (pinfunction "VDD1_B2") (pintype "power_in"))
      (node (ref "U10") (pin "C1") (pinfunction "VDDQ3_C1") (pintype "power_in"))
      (node (ref "U10") (pin "C9") (pinfunction "VDDQ4_C9") (pintype "power_in"))
      (node (ref "U10") (pin "D2") (pinfunction "VDDQ5_D2") (pintype "power_in"))
      (node (ref "U10") (pin "D9") (pinfunction "VDD2_D9") (pintype "power_in"))
      (node (ref "U10") (pin "E9") (pinfunction "VDDQ6_E9") (pintype "power_in"))
      (node (ref "U10") (pin "F1") (pinfunction "VDDQ7_F1") (pintype "power_in"))
      (node (ref "U10") (pin "G7") (pinfunction "VDD3_G7") (pintype "power_in"))
      (node (ref "U10") (pin "H2") (pinfunction "VDDQ8_H2") (pintype "power_in"))
      (node (ref "U10") (pin "H9") (pinfunction "VDDQ9_H9") (pintype "power_in"))
      (node (ref "U10") (pin "K2") (pinfunction "VDD4_K2") (pintype "power_in"))
      (node (ref "U10") (pin "K8") (pinfunction "VDD5_K8") (pintype "power_in"))
      (node (ref "U10") (pin "N1") (pinfunction "VDD6_N1") (pintype "power_in"))
      (node (ref "U10") (pin "N9") (pinfunction "VDD7_N9") (pintype "power_in"))
      (node (ref "U10") (pin "R1") (pinfunction "VDD8_R1") (pintype "power_in"))
      (node (ref "U10") (pin "R9") (pinfunction "VDD9_R9") (pintype "power_in"))
      (node (ref "U3") (pin "R18") (pinfunction "NVCC_DRAM_1_R18") (pintype "power_in"))
      (node (ref "U3") (pin "T18") (pinfunction "NVCC_DRAM_2_T18") (pintype "power_in"))
      (node (ref "U3") (pin "U18") (pinfunction "NVCC_DRAM_3_U18") (pintype "power_in"))
      (node (ref "U3") (pin "V10") (pinfunction "NVCC_DRAM_4_V10") (pintype "power_in"))
      (node (ref "U3") (pin "V11") (pinfunction "NVCC_DRAM_5_V11") (pintype "power_in"))
      (node (ref "U3") (pin "V12") (pinfunction "NVCC_DRAM_6_V12") (pintype "power_in"))
      (node (ref "U3") (pin "V13") (pinfunction "NVCC_DRAM_7_V13") (pintype "power_in"))
      (node (ref "U3") (pin "V14") (pinfunction "NVCC_DRAM_8_V14") (pintype "power_in"))
      (node (ref "U3") (pin "V15") (pinfunction "NVCC_DRAM_9_V15") (pintype "power_in"))
      (node (ref "U3") (pin "V16") (pinfunction "NVCC_DRAM_10_V16") (pintype "power_in"))
      (node (ref "U3") (pin "V17") (pinfunction "NVCC_DRAM_11_V17") (pintype "power_in"))
      (node (ref "U3") (pin "V18") (pinfunction "NVCC_DRAM_12_V18") (pintype "power_in"))
      (node (ref "U3") (pin "V9") (pinfunction "NVCC_DRAM_13_V9") (pintype "power_in"))
      (node (ref "U7") (pin "A1") (pinfunction "VDDQ1_A1") (pintype "power_in"))
      (node (ref "U7") (pin "A8") (pinfunction "VDDQ2_A8") (pintype "power_in"))
      (node (ref "U7") (pin "B2") (pinfunction "VDD1_B2") (pintype "power_in"))
      (node (ref "U7") (pin "C1") (pinfunction "VDDQ3_C1") (pintype "power_in"))
      (node (ref "U7") (pin "C9") (pinfunction "VDDQ4_C9") (pintype "power_in"))
      (node (ref "U7") (pin "D2") (pinfunction "VDDQ5_D2") (pintype "power_in"))
      (node (ref "U7") (pin "D9") (pinfunction "VDD2_D9") (pintype "power_in"))
      (node (ref "U7") (pin "E9") (pinfunction "VDDQ6_E9") (pintype "power_in"))
      (node (ref "U7") (pin "F1") (pinfunction "VDDQ7_F1") (pintype "power_in"))
      (node (ref "U7") (pin "G7") (pinfunction "VDD3_G7") (pintype "power_in"))
      (node (ref "U7") (pin "H2") (pinfunction "VDDQ8_H2") (pintype "power_in"))
      (node (ref "U7") (pin "H9") (pinfunction "VDDQ9_H9") (pintype "power_in"))
      (node (ref "U7") (pin "K2") (pinfunction "VDD4_K2") (pintype "power_in"))
      (node (ref "U7") (pin "K8") (pinfunction "VDD5_K8") (pintype "power_in"))
      (node (ref "U7") (pin "N1") (pinfunction "VDD6_N1") (pintype "power_in"))
      (node (ref "U7") (pin "N9") (pinfunction "VDD7_N9") (pintype "power_in"))
      (node (ref "U7") (pin "R1") (pinfunction "VDD8_R1") (pintype "power_in"))
      (node (ref "U7") (pin "R9") (pinfunction "VDD9_R9") (pintype "power_in"))
      (node (ref "U8") (pin "A1") (pinfunction "VDDQ1_A1") (pintype "power_in"))
      (node (ref "U8") (pin "A8") (pinfunction "VDDQ2_A8") (pintype "power_in"))
      (node (ref "U8") (pin "B2") (pinfunction "VDD1_B2") (pintype "power_in"))
      (node (ref "U8") (pin "C1") (pinfunction "VDDQ3_C1") (pintype "power_in"))
      (node (ref "U8") (pin "C9") (pinfunction "VDDQ4_C9") (pintype "power_in"))
      (node (ref "U8") (pin "D2") (pinfunction "VDDQ5_D2") (pintype "power_in"))
      (node (ref "U8") (pin "D9") (pinfunction "VDD2_D9") (pintype "power_in"))
      (node (ref "U8") (pin "E9") (pinfunction "VDDQ6_E9") (pintype "power_in"))
      (node (ref "U8") (pin "F1") (pinfunction "VDDQ7_F1") (pintype "power_in"))
      (node (ref "U8") (pin "G7") (pinfunction "VDD3_G7") (pintype "power_in"))
      (node (ref "U8") (pin "H2") (pinfunction "VDDQ8_H2") (pintype "power_in"))
      (node (ref "U8") (pin "H9") (pinfunction "VDDQ9_H9") (pintype "power_in"))
      (node (ref "U8") (pin "K2") (pinfunction "VDD4_K2") (pintype "power_in"))
      (node (ref "U8") (pin "K8") (pinfunction "VDD5_K8") (pintype "power_in"))
      (node (ref "U8") (pin "N1") (pinfunction "VDD6_N1") (pintype "power_in"))
      (node (ref "U8") (pin "N9") (pinfunction "VDD7_N9") (pintype "power_in"))
      (node (ref "U8") (pin "R1") (pinfunction "VDD8_R1") (pintype "power_in"))
      (node (ref "U8") (pin "R9") (pinfunction "VDD9_R9") (pintype "power_in"))
      (node (ref "U9") (pin "A1") (pinfunction "VDDQ1_A1") (pintype "power_in"))
      (node (ref "U9") (pin "A8") (pinfunction "VDDQ2_A8") (pintype "power_in"))
      (node (ref "U9") (pin "B2") (pinfunction "VDD1_B2") (pintype "power_in"))
      (node (ref "U9") (pin "C1") (pinfunction "VDDQ3_C1") (pintype "power_in"))
      (node (ref "U9") (pin "C9") (pinfunction "VDDQ4_C9") (pintype "power_in"))
      (node (ref "U9") (pin "D2") (pinfunction "VDDQ5_D2") (pintype "power_in"))
      (node (ref "U9") (pin "D9") (pinfunction "VDD2_D9") (pintype "power_in"))
      (node (ref "U9") (pin "E9") (pinfunction "VDDQ6_E9") (pintype "power_in"))
      (node (ref "U9") (pin "F1") (pinfunction "VDDQ7_F1") (pintype "power_in"))
      (node (ref "U9") (pin "G7") (pinfunction "VDD3_G7") (pintype "power_in"))
      (node (ref "U9") (pin "H2") (pinfunction "VDDQ8_H2") (pintype "power_in"))
      (node (ref "U9") (pin "H9") (pinfunction "VDDQ9_H9") (pintype "power_in"))
      (node (ref "U9") (pin "K2") (pinfunction "VDD4_K2") (pintype "power_in"))
      (node (ref "U9") (pin "K8") (pinfunction "VDD5_K8") (pintype "power_in"))
      (node (ref "U9") (pin "N1") (pinfunction "VDD6_N1") (pintype "power_in"))
      (node (ref "U9") (pin "N9") (pinfunction "VDD7_N9") (pintype "power_in"))
      (node (ref "U9") (pin "R1") (pinfunction "VDD8_R1") (pintype "power_in"))
      (node (ref "U9") (pin "R9") (pinfunction "VDD9_R9") (pintype "power_in"))
    )
    (net (code "133") (name "unconnected-(U3J-DRAM_CS1-PadAD17)") (class "Default")
      (node (ref "U3") (pin "AD17") (pinfunction "DRAM_CS1_AD17") (pintype "output"))
    )
    (net (code "134") (name "unconnected-(U3J-DRAM_SDCKE1-PadAA11)") (class "Default")
      (node (ref "U3") (pin "AA11") (pinfunction "DRAM_SDCKE1_AA11") (pintype "output"))
    )
    (net (code "135") (name "unconnected-(U3J-DRAM_SDODT1-PadAB17)") (class "Default")
      (node (ref "U3") (pin "AB17") (pinfunction "DRAM_SDODT1_AB17") (pintype "output"))
    )
    (net (code "136") (name "unconnected-(U7-NC_J1-PadJ1)") (class "Default")
      (node (ref "U7") (pin "J1") (pinfunction "NC_J1_J1") (pintype "passive"))
    )
    (net (code "137") (name "unconnected-(U7-NC_J9-PadJ9)") (class "Default")
      (node (ref "U7") (pin "J9") (pinfunction "NC_J9_J9") (pintype "passive"))
    )
    (net (code "138") (name "unconnected-(U7-NC_L1-PadL1)") (class "Default")
      (node (ref "U7") (pin "L1") (pinfunction "NC_L1_L1") (pintype "passive"))
    )
    (net (code "139") (name "unconnected-(U7-NC_L9-PadL9)") (class "Default")
      (node (ref "U7") (pin "L9") (pinfunction "NC_L9_L9") (pintype "passive"))
    )
    (net (code "140") (name "unconnected-(U8-NC_J1-PadJ1)") (class "Default")
      (node (ref "U8") (pin "J1") (pinfunction "NC_J1_J1") (pintype "passive"))
    )
    (net (code "141") (name "unconnected-(U8-NC_J9-PadJ9)") (class "Default")
      (node (ref "U8") (pin "J9") (pinfunction "NC_J9_J9") (pintype "passive"))
    )
    (net (code "142") (name "unconnected-(U8-NC_L1-PadL1)") (class "Default")
      (node (ref "U8") (pin "L1") (pinfunction "NC_L1_L1") (pintype "passive"))
    )
    (net (code "143") (name "unconnected-(U8-NC_L9-PadL9)") (class "Default")
      (node (ref "U8") (pin "L9") (pinfunction "NC_L9_L9") (pintype "passive"))
    )
    (net (code "144") (name "unconnected-(U9-NC_J1-PadJ1)") (class "Default")
      (node (ref "U9") (pin "J1") (pinfunction "NC_J1_J1") (pintype "passive"))
    )
    (net (code "145") (name "unconnected-(U9-NC_J9-PadJ9)") (class "Default")
      (node (ref "U9") (pin "J9") (pinfunction "NC_J9_J9") (pintype "passive"))
    )
    (net (code "146") (name "unconnected-(U9-NC_L1-PadL1)") (class "Default")
      (node (ref "U9") (pin "L1") (pinfunction "NC_L1_L1") (pintype "passive"))
    )
    (net (code "147") (name "unconnected-(U9-NC_L9-PadL9)") (class "Default")
      (node (ref "U9") (pin "L9") (pinfunction "NC_L9_L9") (pintype "passive"))
    )
    (net (code "148") (name "unconnected-(U10-NC_J1-PadJ1)") (class "Default")
      (node (ref "U10") (pin "J1") (pinfunction "NC_J1_J1") (pintype "passive"))
    )
    (net (code "149") (name "unconnected-(U10-NC_J9-PadJ9)") (class "Default")
      (node (ref "U10") (pin "J9") (pinfunction "NC_J9_J9") (pintype "passive"))
    )
    (net (code "150") (name "unconnected-(U10-NC_L1-PadL1)") (class "Default")
      (node (ref "U10") (pin "L1") (pinfunction "NC_L1_L1") (pintype "passive"))
    )
    (net (code "151") (name "unconnected-(U10-NC_L9-PadL9)") (class "Default")
      (node (ref "U10") (pin "L9") (pinfunction "NC_L9_L9") (pintype "passive"))
    )
  )
)
